# PIO-Dev-3.net
KiCad netlist of a schematic drawn in EAGLE
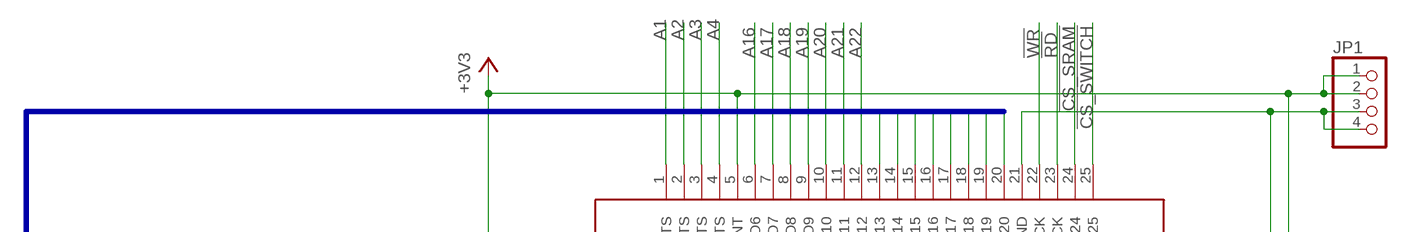
[diagram p0: schematic, sheet 1, part 1 of 3]
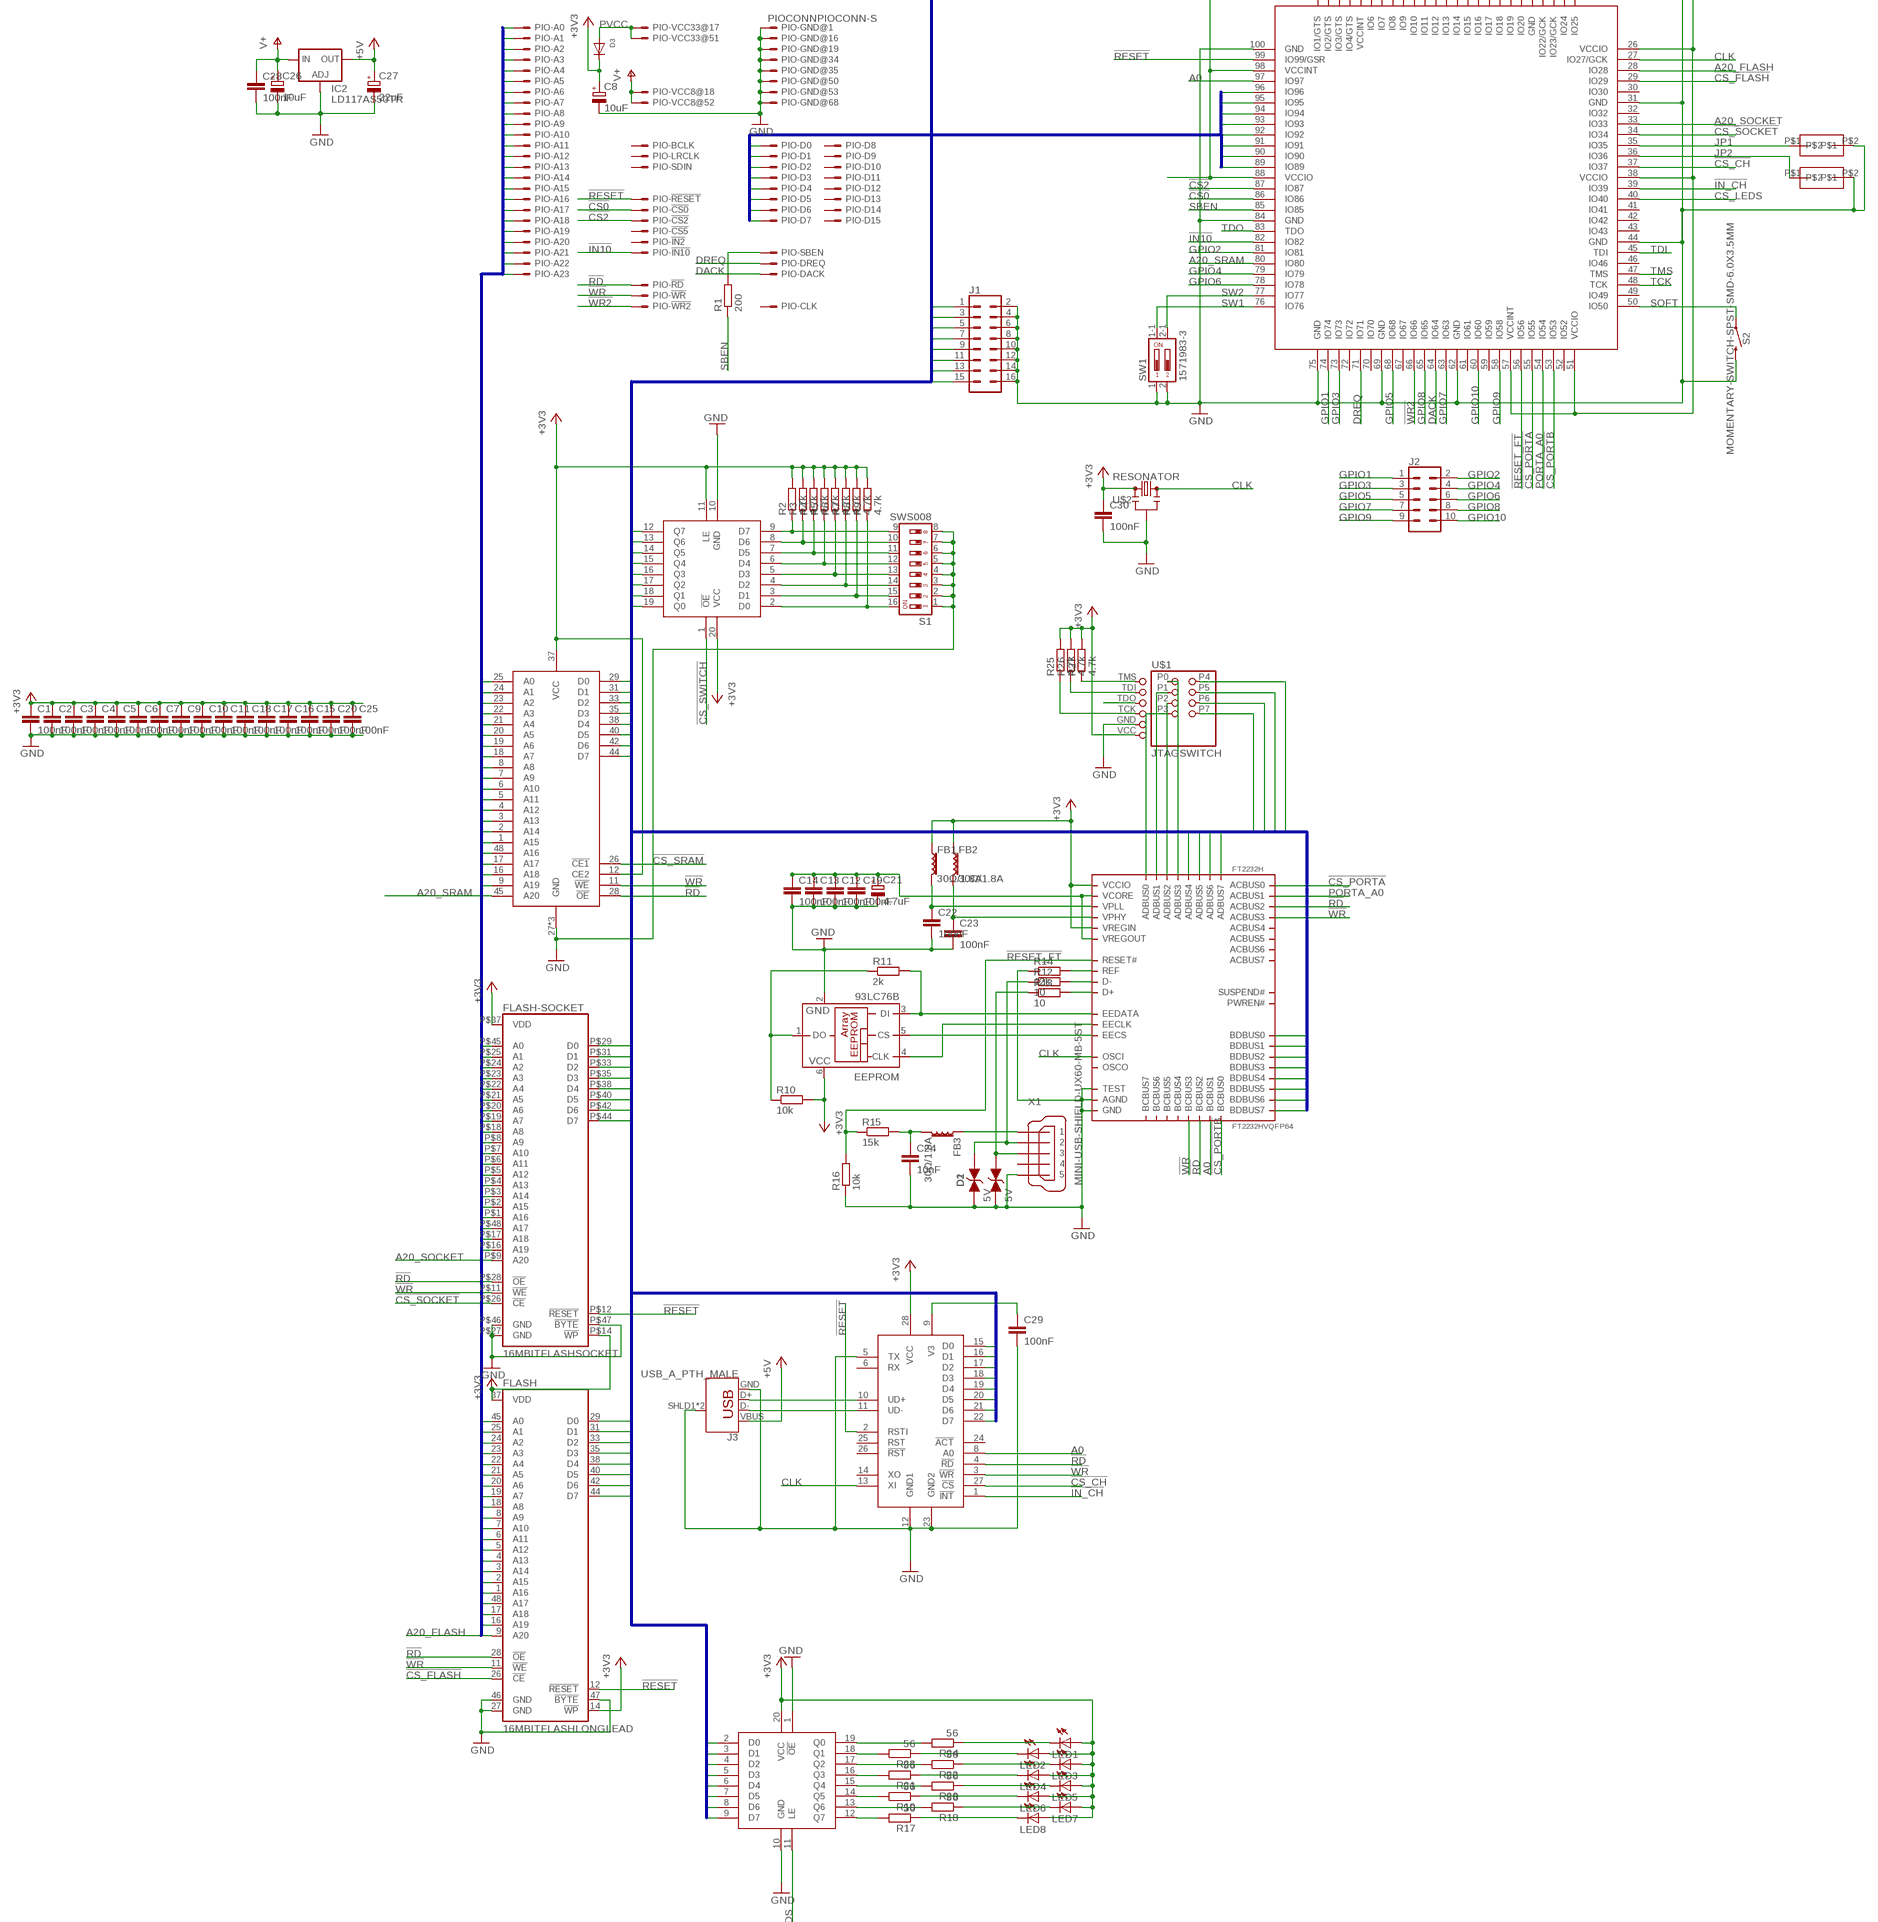
[diagram p1: schematic, sheet 1, part 2 of 3]
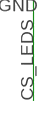
[diagram p2: schematic, sheet 1, part 3 of 3]

(export (version "E")
  (design (tool "Eeschema 10.0.6"))
  (components
    (comp (ref "C1")
      (value "100nF")
      (footprint "eagle-import:C0402K")
      (libsource (lib "eagle-import") (part "C-EUC0402K"))
    )
    (comp (ref "C2")
      (value "100nF")
      (footprint "eagle-import:C0402K")
      (libsource (lib "eagle-import") (part "C-EUC0402K"))
    )
    (comp (ref "C3")
      (value "100nF")
      (footprint "eagle-import:C0402K")
      (libsource (lib "eagle-import") (part "C-EUC0402K"))
    )
    (comp (ref "C4")
      (value "100nF")
      (footprint "eagle-import:C0402K")
      (libsource (lib "eagle-import") (part "C-EUC0402K"))
    )
    (comp (ref "C5")
      (value "100nF")
      (footprint "eagle-import:C0402K")
      (libsource (lib "eagle-import") (part "C-EUC0402K"))
    )
    (comp (ref "C6")
      (value "100nF")
      (footprint "eagle-import:C0402K")
      (libsource (lib "eagle-import") (part "C-EUC0402K"))
    )
    (comp (ref "C7")
      (value "100nF")
      (footprint "eagle-import:C0402K")
      (libsource (lib "eagle-import") (part "C-EUC0402K"))
    )
    (comp (ref "C8")
      (value "10uF")
      (footprint "eagle-import:A_3216-18W")
      (libsource (lib "eagle-import") (part "CPOL-EUA/3216-18W"))
    )
    (comp (ref "C9")
      (value "100nF")
      (footprint "eagle-import:C0402K")
      (libsource (lib "eagle-import") (part "C-EUC0402K"))
    )
    (comp (ref "C10")
      (value "100nF")
      (footprint "eagle-import:C0402K")
      (libsource (lib "eagle-import") (part "C-EUC0402K"))
    )
    (comp (ref "C11")
      (value "100nF")
      (footprint "eagle-import:C0402K")
      (libsource (lib "eagle-import") (part "C-EUC0402K"))
    )
    (comp (ref "C12")
      (value "100nF")
      (footprint "eagle-import:C0603K")
      (libsource (lib "eagle-import") (part "C-EUC0603K"))
    )
    (comp (ref "C13")
      (value "100nF")
      (footprint "eagle-import:C0603K")
      (libsource (lib "eagle-import") (part "C-EUC0603K"))
    )
    (comp (ref "C14")
      (value "100nF")
      (footprint "eagle-import:C0603K")
      (libsource (lib "eagle-import") (part "C-EUC0603K"))
    )
    (comp (ref "C15")
      (value "100nF")
      (footprint "eagle-import:C0603K")
      (libsource (lib "eagle-import") (part "C-EUC0603K"))
    )
    (comp (ref "C16")
      (value "100nF")
      (footprint "eagle-import:C0603K")
      (libsource (lib "eagle-import") (part "C-EUC0603K"))
    )
    (comp (ref "C17")
      (value "100nF")
      (footprint "eagle-import:C0603K")
      (libsource (lib "eagle-import") (part "C-EUC0603K"))
    )
    (comp (ref "C18")
      (value "100nF")
      (footprint "eagle-import:C0603K")
      (libsource (lib "eagle-import") (part "C-EUC0603K"))
    )
    (comp (ref "C19")
      (value "100nF")
      (footprint "eagle-import:C0603K")
      (libsource (lib "eagle-import") (part "C-EUC0603K"))
    )
    (comp (ref "C20")
      (value "100nF")
      (footprint "eagle-import:C0603K")
      (libsource (lib "eagle-import") (part "C-EUC0603K"))
    )
    (comp (ref "C21")
      (value "4.7uF")
      (footprint "eagle-import:A_3216-18W")
      (libsource (lib "eagle-import") (part "CPOL-EUA/3216-18W"))
    )
    (comp (ref "C22")
      (value "100nF")
      (footprint "eagle-import:C0603K")
      (libsource (lib "eagle-import") (part "C-EUC0603K"))
    )
    (comp (ref "C23")
      (value "100nF")
      (footprint "eagle-import:C0603K")
      (libsource (lib "eagle-import") (part "C-EUC0603K"))
    )
    (comp (ref "C24")
      (value "10nF")
      (footprint "eagle-import:C0402K")
      (libsource (lib "eagle-import") (part "C-EUC0402K"))
    )
    (comp (ref "C25")
      (value "100nF")
      (footprint "eagle-import:C0402K")
      (libsource (lib "eagle-import") (part "C-EUC0402K"))
    )
    (comp (ref "C26")
      (value "10uF")
      (footprint "eagle-import:A_3216-18W")
      (libsource (lib "eagle-import") (part "CPOL-EUA/3216-18W"))
    )
    (comp (ref "C27")
      (value "22uF")
      (footprint "eagle-import:A_3216-18W")
      (libsource (lib "eagle-import") (part "CPOL-EUA/3216-18W"))
    )
    (comp (ref "C28")
      (value "100nF")
      (footprint "eagle-import:C0603K")
      (libsource (lib "eagle-import") (part "C-EUC0603K"))
    )
    (comp (ref "C29")
      (value "100nF")
      (footprint "eagle-import:C0402K")
      (libsource (lib "eagle-import") (part "C-EUC0402K"))
    )
    (comp (ref "C30")
      (value "100nF")
      (footprint "eagle-import:C0603K")
      (libsource (lib "eagle-import") (part "C-EUC0603K"))
    )
    (comp (ref "CH")
      (value "CH375B")
      (footprint "eagle-import:SOP28-LL")
      (libsource (lib "eagle-import") (part "CH375B"))
    )
    (comp (ref "CPLD")
      (value "XC95144XL-100")
      (footprint "eagle-import:TQFP100")
      (libsource (lib "eagle-import") (part "XC95144XL-100"))
    )
    (comp (ref "D1")
      (value "5V")
      (footprint "eagle-import:WE-VE_0603")
      (libsource (lib "eagle-import") (part "WE-VE_0603_82356050050"))
    )
    (comp (ref "D2")
      (value "5V")
      (footprint "eagle-import:WE-VE_0603")
      (libsource (lib "eagle-import") (part "WE-VE_0603_82356050050"))
    )
    (comp (ref "D3")
      (value "DIODESOD-123")
      (footprint "eagle-import:SOD-123")
      (libsource (lib "eagle-import") (part "DIODESOD-123"))
    )
    (comp (ref "EEPROM")
      (value "93LC76B")
      (footprint "eagle-import:SOT23-6")
      (fields (field (name "MF") "MICROCHIP") (field (name "MPN") "93LC76BT-I/OT"))
      (libsource (lib "eagle-import") (part "9376?BLC"))
    )
    (comp (ref "FB1")
      (value "30Ω/1.8A")
      (footprint "eagle-import:0603")
      (libsource (lib "eagle-import") (part "FERRITE_BEAD-0603"))
    )
    (comp (ref "FB2")
      (value "30Ω/1.8A")
      (footprint "eagle-import:0603")
      (libsource (lib "eagle-import") (part "FERRITE_BEAD-0603"))
    )
    (comp (ref "FB3")
      (value "30Ω/1.8A")
      (footprint "eagle-import:0603")
      (libsource (lib "eagle-import") (part "FERRITE_BEAD-0603"))
    )
    (comp (ref "FLASH")
      (value "16MBITFLASHLONGLEAD")
      (footprint "eagle-import:TSOP48-LL")
      (libsource (lib "eagle-import") (part "16MBITFLASHLONGLEAD"))
    )
    (comp (ref "FLASH-SOCKET")
      (value "16MBITFLASHSOCKET")
      (footprint "eagle-import:TSOP48-ADAPTER")
      (libsource (lib "eagle-import") (part "16MBITFLASHSOCKET"))
    )
    (comp (ref "FT2232H")
      (value "FT2232HVQFP64")
      (footprint "eagle-import:VQFP64")
      (libsource (lib "eagle-import") (part "FT2232HVQFP64"))
    )
    (comp (ref "IC2")
      (value "LD117AS50TR")
      (footprint "eagle-import:SOT223")
      (libsource (lib "eagle-import") (part "LD117A?S50TR"))
    )
    (comp (ref "J1")
      (value "CONN_08X2SHD_SMD")
      (footprint "eagle-import:2X8-SHROUDED_SMD")
      (libsource (lib "eagle-import") (part "CONN_08X2SHD_SMD"))
    )
    (comp (ref "J2")
      (value "CONN_05X2SHD_SMD")
      (footprint "eagle-import:2X5-SHROUDED_SMD")
      (libsource (lib "eagle-import") (part "CONN_05X2SHD_SMD"))
    )
    (comp (ref "J3")
      (value "USB_A_PTH_MALE")
      (footprint "eagle-import:USB-A-H")
      (libsource (lib "eagle-import") (part "USB_A_PTH_MALE"))
    )
    (comp (ref "JP1")
      (value "PINHD-1X4")
      (footprint "eagle-import:1X04")
      (libsource (lib "eagle-import") (part "PINHD-1X4"))
    )
    (comp (ref "LED1")
      (value "LEDCHIPLED_1206")
      (footprint "eagle-import:CHIPLED_1206")
      (libsource (lib "eagle-import") (part "LEDCHIPLED_1206"))
    )
    (comp (ref "LED2")
      (value "LEDCHIPLED_1206")
      (footprint "eagle-import:CHIPLED_1206")
      (libsource (lib "eagle-import") (part "LEDCHIPLED_1206"))
    )
    (comp (ref "LED3")
      (value "LEDCHIPLED_1206")
      (footprint "eagle-import:CHIPLED_1206")
      (libsource (lib "eagle-import") (part "LEDCHIPLED_1206"))
    )
    (comp (ref "LED4")
      (value "LEDCHIPLED_1206")
      (footprint "eagle-import:CHIPLED_1206")
      (libsource (lib "eagle-import") (part "LEDCHIPLED_1206"))
    )
    (comp (ref "LED5")
      (value "LEDCHIPLED_1206")
      (footprint "eagle-import:CHIPLED_1206")
      (libsource (lib "eagle-import") (part "LEDCHIPLED_1206"))
    )
    (comp (ref "LED6")
      (value "LEDCHIPLED_1206")
      (footprint "eagle-import:CHIPLED_1206")
      (libsource (lib "eagle-import") (part "LEDCHIPLED_1206"))
    )
    (comp (ref "LED7")
      (value "LEDCHIPLED_1206")
      (footprint "eagle-import:CHIPLED_1206")
      (libsource (lib "eagle-import") (part "LEDCHIPLED_1206"))
    )
    (comp (ref "LED8")
      (value "LEDCHIPLED_1206")
      (footprint "eagle-import:CHIPLED_1206")
      (libsource (lib "eagle-import") (part "LEDCHIPLED_1206"))
    )
    (comp (ref "LEDS")
      (value "74LVC573APW")
      (footprint "eagle-import:TSSOP20-LL")
      (libsource (lib "eagle-import") (part "74LVC573APW"))
    )
    (comp (ref "PIO")
      (value "PIOCONNPIOCONN-S")
      (footprint "eagle-import:PIOCONN")
      (libsource (lib "eagle-import") (part "PIOCONNPIOCONN-S"))
    )
    (comp (ref "R1")
      (value "200")
      (footprint "eagle-import:R0402")
      (libsource (lib "eagle-import") (part "R-EU_R0402"))
    )
    (comp (ref "R2")
      (value "4.7k")
      (footprint "eagle-import:R0402")
      (libsource (lib "eagle-import") (part "R-EU_R0402"))
    )
    (comp (ref "R3")
      (value "4.7k")
      (footprint "eagle-import:R0402")
      (libsource (lib "eagle-import") (part "R-EU_R0402"))
    )
    (comp (ref "R4")
      (value "4.7k")
      (footprint "eagle-import:R0402")
      (libsource (lib "eagle-import") (part "R-EU_R0402"))
    )
    (comp (ref "R5")
      (value "4.7k")
      (footprint "eagle-import:R0402")
      (libsource (lib "eagle-import") (part "R-EU_R0402"))
    )
    (comp (ref "R6")
      (value "4.7k")
      (footprint "eagle-import:R0402")
      (libsource (lib "eagle-import") (part "R-EU_R0402"))
    )
    (comp (ref "R7")
      (value "4.7k")
      (footprint "eagle-import:R0402")
      (libsource (lib "eagle-import") (part "R-EU_R0402"))
    )
    (comp (ref "R8")
      (value "4.7k")
      (footprint "eagle-import:R0402")
      (libsource (lib "eagle-import") (part "R-EU_R0402"))
    )
    (comp (ref "R9")
      (value "4.7k")
      (footprint "eagle-import:R0402")
      (libsource (lib "eagle-import") (part "R-EU_R0402"))
    )
    (comp (ref "R10")
      (value "10k")
      (footprint "eagle-import:R0402")
      (libsource (lib "eagle-import") (part "R-EU_R0402"))
    )
    (comp (ref "R11")
      (value "2k")
      (footprint "eagle-import:R0402")
      (libsource (lib "eagle-import") (part "R-EU_R0402"))
    )
    (comp (ref "R12")
      (value "10")
      (footprint "eagle-import:R0402")
      (libsource (lib "eagle-import") (part "R-EU_R0402"))
    )
    (comp (ref "R13")
      (value "10")
      (footprint "eagle-import:R0402")
      (libsource (lib "eagle-import") (part "R-EU_R0402"))
    )
    (comp (ref "R14")
      (value "12k")
      (footprint "eagle-import:R0402")
      (libsource (lib "eagle-import") (part "R-EU_R0402"))
    )
    (comp (ref "R15")
      (value "15k")
      (footprint "eagle-import:R0402")
      (libsource (lib "eagle-import") (part "R-EU_R0402"))
    )
    (comp (ref "R16")
      (value "10k")
      (footprint "eagle-import:R0402")
      (libsource (lib "eagle-import") (part "R-EU_R0402"))
    )
    (comp (ref "R17")
      (value "56")
      (footprint "eagle-import:R0603")
      (libsource (lib "eagle-import") (part "R-EU_R0603"))
    )
    (comp (ref "R18")
      (value "56")
      (footprint "eagle-import:R0603")
      (libsource (lib "eagle-import") (part "R-EU_R0603"))
    )
    (comp (ref "R19")
      (value "56")
      (footprint "eagle-import:R0603")
      (libsource (lib "eagle-import") (part "R-EU_R0603"))
    )
    (comp (ref "R20")
      (value "56")
      (footprint "eagle-import:R0603")
      (libsource (lib "eagle-import") (part "R-EU_R0603"))
    )
    (comp (ref "R21")
      (value "56")
      (footprint "eagle-import:R0603")
      (libsource (lib "eagle-import") (part "R-EU_R0603"))
    )
    (comp (ref "R22")
      (value "56")
      (footprint "eagle-import:R0603")
      (libsource (lib "eagle-import") (part "R-EU_R0603"))
    )
    (comp (ref "R23")
      (value "56")
      (footprint "eagle-import:R0603")
      (libsource (lib "eagle-import") (part "R-EU_R0603"))
    )
    (comp (ref "R24")
      (value "56")
      (footprint "eagle-import:R0603")
      (libsource (lib "eagle-import") (part "R-EU_R0603"))
    )
    (comp (ref "R25")
      (value "4.7k")
      (footprint "eagle-import:R0402")
      (libsource (lib "eagle-import") (part "R-EU_R0402"))
    )
    (comp (ref "R26")
      (value "4.7k")
      (footprint "eagle-import:R0402")
      (libsource (lib "eagle-import") (part "R-EU_R0402"))
    )
    (comp (ref "R27")
      (value "4.7k")
      (footprint "eagle-import:R0402")
      (libsource (lib "eagle-import") (part "R-EU_R0402"))
    )
    (comp (ref "S1")
      (value "SWS008")
      (footprint "eagle-import:SMS-008")
      (libsource (lib "eagle-import") (part "SWS008"))
    )
    (comp (ref "S2")
      (value "MOMENTARY-SWITCH-SPST-SMD-6.0X3.5MM")
      (footprint "eagle-import:TACTILE_SWITCH_SMD_6.0X3.5MM")
      (libsource (lib "eagle-import") (part "MOMENTARY-SWITCH-SPST-SMD-6.0X3.5MM"))
    )
    (comp (ref "SRAM")
      (value "CY62167EV30LL")
      (footprint "eagle-import:TSOP48-LL")
      (libsource (lib "eagle-import") (part "CY62167EV30LL"))
    )
    (comp (ref "SW1")
      (value "1571983-3")
      (footprint "eagle-import:1571983-3")
      (fields
        (field (name "DIGIKEY_PARTNO") "450-2128-2-ND")
        (field (name "MANUFACTURER") "TE Connectivity ALCOSWITCH Switches")
        (field (name "CREATED_BY") "PCBLayout.com")
      )
      (libsource (lib "eagle-import") (part "1571983-3"))
    )
    (comp (ref "SWITCH")
      (value "74LVC573APW")
      (footprint "eagle-import:TSSOP20-LL")
      (libsource (lib "eagle-import") (part "74LVC573APW"))
    )
    (comp (ref "U$1")
      (value "JTAGSWITCH")
      (footprint "eagle-import:JTAGSWITCH")
      (libsource (lib "eagle-import") (part "JTAGSWITCH"))
    )
    (comp (ref "U$2")
      (value "RESONATOR")
      (footprint "eagle-import:RESONATOR")
      (libsource (lib "eagle-import") (part "RESONATOR"))
    )
    (comp (ref "U$3")
      (value "SMD-JUMPER")
      (footprint "eagle-import:SMD-JUMPER")
      (libsource (lib "eagle-import") (part "SMD-JUMPER"))
    )
    (comp (ref "U$4")
      (value "SMD-JUMPER")
      (footprint "eagle-import:SMD-JUMPER")
      (libsource (lib "eagle-import") (part "SMD-JUMPER"))
    )
    (comp (ref "X1")
      (value "MINI-USB-SHIELD-UX60-MB-5ST")
      (footprint "eagle-import:UX60-MB-5ST")
      (libsource (lib "eagle-import") (part "MINI-USB-SHIELD-UX60-MB-5ST"))
    )
  )
  (nets
    (net (code "1") (name "+3V3") (class "Default")
      (node (ref "C1") (pin "1") (pinfunction "1_1") (pintype "passive"))
      (node (ref "C10") (pin "1") (pinfunction "1_1") (pintype "passive"))
      (node (ref "C11") (pin "1") (pinfunction "1_1") (pintype "passive"))
      (node (ref "C15") (pin "1") (pinfunction "1_1") (pintype "passive"))
      (node (ref "C16") (pin "1") (pinfunction "1_1") (pintype "passive"))
      (node (ref "C17") (pin "1") (pinfunction "1_1") (pintype "passive"))
      (node (ref "C18") (pin "1") (pinfunction "1_1") (pintype "passive"))
      (node (ref "C2") (pin "1") (pinfunction "1_1") (pintype "passive"))
      (node (ref "C20") (pin "1") (pinfunction "1_1") (pintype "passive"))
      (node (ref "C25") (pin "1") (pinfunction "1_1") (pintype "passive"))
      (node (ref "C3") (pin "1") (pinfunction "1_1") (pintype "passive"))
      (node (ref "C30") (pin "1") (pinfunction "1_1") (pintype "passive"))
      (node (ref "C4") (pin "1") (pinfunction "1_1") (pintype "passive"))
      (node (ref "C5") (pin "1") (pinfunction "1_1") (pintype "passive"))
      (node (ref "C6") (pin "1") (pinfunction "1_1") (pintype "passive"))
      (node (ref "C7") (pin "1") (pinfunction "1_1") (pintype "passive"))
      (node (ref "C8") (pin "+") (pinfunction "+_+") (pintype "passive"))
      (node (ref "C9") (pin "1") (pinfunction "1_1") (pintype "passive"))
      (node (ref "CH") (pin "28") (pinfunction "VCC_28") (pintype "bidirectional"))
      (node (ref "CPLD") (pin "26") (pinfunction "VCCIO_26") (pintype "bidirectional"))
      (node (ref "CPLD") (pin "38") (pinfunction "VCCIO_38") (pintype "bidirectional"))
      (node (ref "CPLD") (pin "5") (pinfunction "VCCINT_5") (pintype "bidirectional"))
      (node (ref "CPLD") (pin "51") (pinfunction "VCCIO_51") (pintype "bidirectional"))
      (node (ref "CPLD") (pin "57") (pinfunction "VCCINT_57") (pintype "bidirectional"))
      (node (ref "CPLD") (pin "88") (pinfunction "VCCIO_88") (pintype "bidirectional"))
      (node (ref "CPLD") (pin "98") (pinfunction "VCCINT_98") (pintype "bidirectional"))
      (node (ref "D3") (pin "C") (pinfunction "C_C") (pintype "passive"))
      (node (ref "EEPROM") (pin "6") (pinfunction "VCC_6") (pintype "power_in"))
      (node (ref "FB1") (pin "1") (pinfunction "1_1") (pintype "passive"))
      (node (ref "FB2") (pin "1") (pinfunction "1_1") (pintype "passive"))
      (node (ref "FLASH") (pin "14") (pinfunction "~{WP}_14") (pintype "bidirectional"))
      (node (ref "FLASH") (pin "37") (pinfunction "VDD_37") (pintype "power_in"))
      (node (ref "FLASH-SOCKET") (pin "P$14") (pinfunction "~{WP}_P$14") (pintype "bidirectional"))
      (node (ref "FLASH-SOCKET") (pin "P$37") (pinfunction "VDD_P$37") (pintype "power_in"))
      (node (ref "FT2232H") (pin "20") (pinfunction "VCCIO_20") (pintype "bidirectional"))
      (node (ref "FT2232H") (pin "31") (pinfunction "VCCIO_31") (pintype "bidirectional"))
      (node (ref "FT2232H") (pin "42") (pinfunction "VCCIO_42") (pintype "bidirectional"))
      (node (ref "FT2232H") (pin "50") (pinfunction "VREGIN_50") (pintype "bidirectional"))
      (node (ref "FT2232H") (pin "56") (pinfunction "VCCIO_56") (pintype "bidirectional"))
      (node (ref "JP1") (pin "1") (pinfunction "1_1") (pintype "passive"))
      (node (ref "JP1") (pin "2") (pinfunction "2_2") (pintype "passive"))
      (node (ref "LED1") (pin "A") (pinfunction "A_A") (pintype "passive"))
      (node (ref "LED2") (pin "A") (pinfunction "A_A") (pintype "passive"))
      (node (ref "LED3") (pin "A") (pinfunction "A_A") (pintype "passive"))
      (node (ref "LED4") (pin "A") (pinfunction "A_A") (pintype "passive"))
      (node (ref "LED5") (pin "A") (pinfunction "A_A") (pintype "passive"))
      (node (ref "LED6") (pin "A") (pinfunction "A_A") (pintype "passive"))
      (node (ref "LED7") (pin "A") (pinfunction "A_A") (pintype "passive"))
      (node (ref "LED8") (pin "A") (pinfunction "A_A") (pintype "passive"))
      (node (ref "LEDS") (pin "20") (pinfunction "VCC_20") (pintype "bidirectional"))
      (node (ref "R10") (pin "2") (pinfunction "2_2") (pintype "passive"))
      (node (ref "R2") (pin "2") (pinfunction "2_2") (pintype "passive"))
      (node (ref "R25") (pin "2") (pinfunction "2_2") (pintype "passive"))
      (node (ref "R26") (pin "2") (pinfunction "2_2") (pintype "passive"))
      (node (ref "R27") (pin "2") (pinfunction "2_2") (pintype "passive"))
      (node (ref "R3") (pin "2") (pinfunction "2_2") (pintype "passive"))
      (node (ref "R4") (pin "2") (pinfunction "2_2") (pintype "passive"))
      (node (ref "R5") (pin "2") (pinfunction "2_2") (pintype "passive"))
      (node (ref "R6") (pin "2") (pinfunction "2_2") (pintype "passive"))
      (node (ref "R7") (pin "2") (pinfunction "2_2") (pintype "passive"))
      (node (ref "R8") (pin "2") (pinfunction "2_2") (pintype "passive"))
      (node (ref "R9") (pin "2") (pinfunction "2_2") (pintype "passive"))
      (node (ref "SRAM") (pin "12") (pinfunction "CE2_12") (pintype "bidirectional"))
      (node (ref "SRAM") (pin "37") (pinfunction "VCC_37") (pintype "bidirectional"))
      (node (ref "SWITCH") (pin "11") (pinfunction "LE_11") (pintype "bidirectional"))
      (node (ref "SWITCH") (pin "20") (pinfunction "VCC_20") (pintype "bidirectional"))
      (node (ref "U$1") (pin "VCC") (pinfunction "VCC_VCC") (pintype "passive"))
      (node (ref "U$2") (pin "P4") (pinfunction "VDD_P4") (pintype "passive"))
    )
    (net (code "2") (name "+5V") (class "Default")
      (node (ref "C27") (pin "+") (pinfunction "+_+") (pintype "passive"))
      (node (ref "IC2") (pin "4") (pinfunction "OUT_4") (pintype "passive"))
      (node (ref "J3") (pin "VBUS") (pinfunction "VBUS_VBUS") (pintype "power_in"))
    )
    (net (code "3") (name "/A0") (class "Default")
      (node (ref "CH") (pin "8") (pinfunction "A0_8") (pintype "bidirectional"))
      (node (ref "CPLD") (pin "97") (pinfunction "IO97_97") (pintype "bidirectional"))
      (node (ref "FLASH") (pin "45") (pinfunction "A0_45") (pintype "input"))
      (node (ref "FLASH-SOCKET") (pin "P$45") (pinfunction "A0_P$45") (pintype "input"))
      (node (ref "FT2232H") (pin "52") (pinfunction "BCBUS1_52") (pintype "bidirectional"))
      (node (ref "PIO") (pin "14") (pinfunction "S_14") (pintype "passive"))
      (node (ref "SRAM") (pin "25") (pinfunction "A0_25") (pintype "bidirectional"))
    )
    (net (code "4") (name "/A1") (class "Default")
      (node (ref "CPLD") (pin "1") (pinfunction "IO1/GTS_1") (pintype "bidirectional"))
      (node (ref "FLASH") (pin "25") (pinfunction "A1_25") (pintype "input"))
      (node (ref "FLASH-SOCKET") (pin "P$25") (pinfunction "A1_P$25") (pintype "input"))
      (node (ref "PIO") (pin "48") (pinfunction "S_48") (pintype "passive"))
      (node (ref "SRAM") (pin "24") (pinfunction "A1_24") (pintype "bidirectional"))
    )
    (net (code "5") (name "/A2") (class "Default")
      (node (ref "CPLD") (pin "2") (pinfunction "IO2/GTS_2") (pintype "bidirectional"))
      (node (ref "FLASH") (pin "24") (pinfunction "A2_24") (pintype "input"))
      (node (ref "FLASH-SOCKET") (pin "P$24") (pinfunction "A2_P$24") (pintype "input"))
      (node (ref "PIO") (pin "15") (pinfunction "S_15") (pintype "passive"))
      (node (ref "SRAM") (pin "23") (pinfunction "A2_23") (pintype "bidirectional"))
    )
    (net (code "6") (name "/A3") (class "Default")
      (node (ref "CPLD") (pin "3") (pinfunction "IO3/GTS_3") (pintype "bidirectional"))
      (node (ref "FLASH") (pin "23") (pinfunction "A3_23") (pintype "input"))
      (node (ref "FLASH-SOCKET") (pin "P$23") (pinfunction "A3_P$23") (pintype "input"))
      (node (ref "PIO") (pin "49") (pinfunction "S_49") (pintype "passive"))
      (node (ref "SRAM") (pin "22") (pinfunction "A3_22") (pintype "bidirectional"))
    )
    (net (code "7") (name "/A4") (class "Default")
      (node (ref "CPLD") (pin "4") (pinfunction "IO4/GTS_4") (pintype "bidirectional"))
      (node (ref "FLASH") (pin "22") (pinfunction "A4_22") (pintype "input"))
      (node (ref "FLASH-SOCKET") (pin "P$22") (pinfunction "A4_P$22") (pintype "input"))
      (node (ref "PIO") (pin "20") (pinfunction "S_20") (pintype "passive"))
      (node (ref "SRAM") (pin "21") (pinfunction "A4_21") (pintype "bidirectional"))
    )
    (net (code "8") (name "/A5") (class "Default")
      (node (ref "FLASH") (pin "21") (pinfunction "A5_21") (pintype "input"))
      (node (ref "FLASH-SOCKET") (pin "P$21") (pinfunction "A5_P$21") (pintype "input"))
      (node (ref "PIO") (pin "54") (pinfunction "S_54") (pintype "passive"))
      (node (ref "SRAM") (pin "20") (pinfunction "A5_20") (pintype "bidirectional"))
    )
    (net (code "9") (name "/A6") (class "Default")
      (node (ref "FLASH") (pin "20") (pinfunction "A6_20") (pintype "input"))
      (node (ref "FLASH-SOCKET") (pin "P$20") (pinfunction "A6_P$20") (pintype "input"))
      (node (ref "PIO") (pin "21") (pinfunction "S_21") (pintype "passive"))
      (node (ref "SRAM") (pin "19") (pinfunction "A6_19") (pintype "bidirectional"))
    )
    (net (code "10") (name "/A7") (class "Default")
      (node (ref "FLASH") (pin "19") (pinfunction "A7_19") (pintype "input"))
      (node (ref "FLASH-SOCKET") (pin "P$19") (pinfunction "A7_P$19") (pintype "input"))
      (node (ref "PIO") (pin "55") (pinfunction "S_55") (pintype "passive"))
      (node (ref "SRAM") (pin "18") (pinfunction "A7_18") (pintype "bidirectional"))
    )
    (net (code "11") (name "/A8") (class "Default")
      (node (ref "FLASH") (pin "18") (pinfunction "A8_18") (pintype "input"))
      (node (ref "FLASH-SOCKET") (pin "P$18") (pinfunction "A8_P$18") (pintype "input"))
      (node (ref "PIO") (pin "22") (pinfunction "S_22") (pintype "passive"))
      (node (ref "SRAM") (pin "8") (pinfunction "A8_8") (pintype "bidirectional"))
    )
    (net (code "12") (name "/A9") (class "Default")
      (node (ref "FLASH") (pin "8") (pinfunction "A9_8") (pintype "input"))
      (node (ref "FLASH-SOCKET") (pin "P$8") (pinfunction "A9_P$8") (pintype "input"))
      (node (ref "PIO") (pin "56") (pinfunction "S_56") (pintype "passive"))
      (node (ref "SRAM") (pin "7") (pinfunction "A9_7") (pintype "bidirectional"))
    )
    (net (code "13") (name "/A10") (class "Default")
      (node (ref "FLASH") (pin "7") (pinfunction "A10_7") (pintype "input"))
      (node (ref "FLASH-SOCKET") (pin "P$7") (pinfunction "A10_P$7") (pintype "input"))
      (node (ref "PIO") (pin "23") (pinfunction "S_23") (pintype "passive"))
      (node (ref "SRAM") (pin "6") (pinfunction "A10_6") (pintype "bidirectional"))
    )
    (net (code "14") (name "/A11") (class "Default")
      (node (ref "FLASH") (pin "6") (pinfunction "A11_6") (pintype "input"))
      (node (ref "FLASH-SOCKET") (pin "P$6") (pinfunction "A11_P$6") (pintype "input"))
      (node (ref "PIO") (pin "57") (pinfunction "S_57") (pintype "passive"))
      (node (ref "SRAM") (pin "5") (pinfunction "A11_5") (pintype "bidirectional"))
    )
    (net (code "15") (name "/A12") (class "Default")
      (node (ref "FLASH") (pin "5") (pinfunction "A12_5") (pintype "input"))
      (node (ref "FLASH-SOCKET") (pin "P$5") (pinfunction "A12_P$5") (pintype "input"))
      (node (ref "PIO") (pin "24") (pinfunction "S_24") (pintype "passive"))
      (node (ref "SRAM") (pin "4") (pinfunction "A12_4") (pintype "bidirectional"))
    )
    (net (code "16") (name "/A13") (class "Default")
      (node (ref "FLASH") (pin "4") (pinfunction "A13_4") (pintype "input"))
      (node (ref "FLASH-SOCKET") (pin "P$4") (pinfunction "A13_P$4") (pintype "input"))
      (node (ref "PIO") (pin "58") (pinfunction "S_58") (pintype "passive"))
      (node (ref "SRAM") (pin "3") (pinfunction "A13_3") (pintype "bidirectional"))
    )
    (net (code "17") (name "/A14") (class "Default")
      (node (ref "FLASH") (pin "3") (pinfunction "A14_3") (pintype "input"))
      (node (ref "FLASH-SOCKET") (pin "P$3") (pinfunction "A14_P$3") (pintype "input"))
      (node (ref "PIO") (pin "25") (pinfunction "S_25") (pintype "passive"))
      (node (ref "SRAM") (pin "2") (pinfunction "A14_2") (pintype "bidirectional"))
    )
    (net (code "18") (name "/A15") (class "Default")
      (node (ref "FLASH") (pin "2") (pinfunction "A15_2") (pintype "input"))
      (node (ref "FLASH-SOCKET") (pin "P$2") (pinfunction "A15_P$2") (pintype "input"))
      (node (ref "PIO") (pin "59") (pinfunction "S_59") (pintype "passive"))
      (node (ref "SRAM") (pin "1") (pinfunction "A15_1") (pintype "bidirectional"))
    )
    (net (code "19") (name "/A16") (class "Default")
      (node (ref "CPLD") (pin "6") (pinfunction "IO6_6") (pintype "bidirectional"))
      (node (ref "FLASH") (pin "1") (pinfunction "A16_1") (pintype "input"))
      (node (ref "FLASH-SOCKET") (pin "P$1") (pinfunction "A16_P$1") (pintype "input"))
      (node (ref "PIO") (pin "26") (pinfunction "S_26") (pintype "passive"))
      (node (ref "SRAM") (pin "48") (pinfunction "A16_48") (pintype "bidirectional"))
    )
    (net (code "20") (name "/A17") (class "Default")
      (node (ref "CPLD") (pin "7") (pinfunction "IO7_7") (pintype "bidirectional"))
      (node (ref "FLASH") (pin "48") (pinfunction "A17_48") (pintype "input"))
      (node (ref "FLASH-SOCKET") (pin "P$48") (pinfunction "A17_P$48") (pintype "input"))
      (node (ref "PIO") (pin "60") (pinfunction "S_60") (pintype "passive"))
      (node (ref "SRAM") (pin "17") (pinfunction "A17_17") (pintype "bidirectional"))
    )
    (net (code "21") (name "/A18") (class "Default")
      (node (ref "CPLD") (pin "8") (pinfunction "IO8_8") (pintype "bidirectional"))
      (node (ref "FLASH") (pin "17") (pinfunction "A18_17") (pintype "input"))
      (node (ref "FLASH-SOCKET") (pin "P$17") (pinfunction "A18_P$17") (pintype "input"))
      (node (ref "PIO") (pin "27") (pinfunction "S_27") (pintype "passive"))
      (node (ref "SRAM") (pin "16") (pinfunction "A18_16") (pintype "bidirectional"))
    )
    (net (code "22") (name "/A19") (class "Default")
      (node (ref "CPLD") (pin "9") (pinfunction "IO9_9") (pintype "bidirectional"))
      (node (ref "FLASH") (pin "16") (pinfunction "A19_16") (pintype "bidirectional"))
      (node (ref "FLASH-SOCKET") (pin "P$16") (pinfunction "A19_P$16") (pintype "bidirectional"))
      (node (ref "PIO") (pin "61") (pinfunction "S_61") (pintype "passive"))
      (node (ref "SRAM") (pin "9") (pinfunction "A19_9") (pintype "bidirectional"))
    )
    (net (code "23") (name "/A20") (class "Default")
      (node (ref "CPLD") (pin "10") (pinfunction "IO10_10") (pintype "bidirectional"))
      (node (ref "PIO") (pin "28") (pinfunction "S_28") (pintype "passive"))
    )
    (net (code "24") (name "/A20_FLASH") (class "Default")
      (node (ref "CPLD") (pin "28") (pinfunction "IO28_28") (pintype "bidirectional"))
      (node (ref "FLASH") (pin "9") (pinfunction "A20_9") (pintype "bidirectional"))
    )
    (net (code "25") (name "/A20_SOCKET") (class "Default")
      (node (ref "CPLD") (pin "33") (pinfunction "IO33_33") (pintype "bidirectional"))
      (node (ref "FLASH-SOCKET") (pin "P$9") (pinfunction "A20_P$9") (pintype "bidirectional"))
    )
    (net (code "26") (name "/A20_SRAM") (class "Default")
      (node (ref "CPLD") (pin "80") (pinfunction "IO80_80") (pintype "bidirectional"))
      (node (ref "SRAM") (pin "45") (pinfunction "A20_45") (pintype "bidirectional"))
    )
    (net (code "27") (name "/A21") (class "Default")
      (node (ref "CPLD") (pin "11") (pinfunction "IO11_11") (pintype "bidirectional"))
      (node (ref "PIO") (pin "62") (pinfunction "S_62") (pintype "passive"))
    )
    (net (code "28") (name "/A22") (class "Default")
      (node (ref "CPLD") (pin "12") (pinfunction "IO12_12") (pintype "bidirectional"))
      (node (ref "PIO") (pin "29") (pinfunction "S_29") (pintype "passive"))
    )
    (net (code "29") (name "/CLK") (class "Default")
      (node (ref "CH") (pin "13") (pinfunction "XI_13") (pintype "bidirectional"))
      (node (ref "CPLD") (pin "27") (pinfunction "IO27/GCK_27") (pintype "bidirectional"))
      (node (ref "FT2232H") (pin "2") (pinfunction "OSCI_2") (pintype "bidirectional"))
      (node (ref "U$2") (pin "P3") (pinfunction "OUTPUT_P3") (pintype "passive"))
    )
    (net (code "30") (name "/CS_LEDS") (class "Default")
      (node (ref "CPLD") (pin "40") (pinfunction "IO40_40") (pintype "bidirectional"))
      (node (ref "LEDS") (pin "11") (pinfunction "LE_11") (pintype "bidirectional"))
    )
    (net (code "31") (name "/D0") (class "Default")
      (node (ref "CH") (pin "15") (pinfunction "D0_15") (pintype "bidirectional"))
      (node (ref "CPLD") (pin "20") (pinfunction "IO20_20") (pintype "bidirectional"))
      (node (ref "FLASH") (pin "29") (pinfunction "D0_29") (pintype "bidirectional"))
      (node (ref "FLASH-SOCKET") (pin "P$29") (pinfunction "D0_P$29") (pintype "bidirectional"))
      (node (ref "FT2232H") (pin "38") (pinfunction "BDBUS0_38") (pintype "bidirectional"))
      (node (ref "J1") (pin "15") (pinfunction "15_15") (pintype "passive"))
      (node (ref "LEDS") (pin "2") (pinfunction "D0_2") (pintype "bidirectional"))
      (node (ref "SRAM") (pin "29") (pinfunction "D0_29") (pintype "bidirectional"))
      (node (ref "SWITCH") (pin "12") (pinfunction "Q7_12") (pintype "bidirectional"))
      (node (ref "U$1") (pin "P4") (pinfunction "P4_P4") (pintype "passive"))
    )
    (net (code "32") (name "/D1") (class "Default")
      (node (ref "CH") (pin "16") (pinfunction "D1_16") (pintype "bidirectional"))
      (node (ref "CPLD") (pin "19") (pinfunction "IO19_19") (pintype "bidirectional"))
      (node (ref "FLASH") (pin "31") (pinfunction "D1_31") (pintype "bidirectional"))
      (node (ref "FLASH-SOCKET") (pin "P$31") (pinfunction "D1_P$31") (pintype "bidirectional"))
      (node (ref "FT2232H") (pin "39") (pinfunction "BDBUS1_39") (pintype "bidirectional"))
      (node (ref "J1") (pin "13") (pinfunction "13_13") (pintype "passive"))
      (node (ref "LEDS") (pin "3") (pinfunction "D1_3") (pintype "bidirectional"))
      (node (ref "SRAM") (pin "31") (pinfunction "D1_31") (pintype "bidirectional"))
      (node (ref "SWITCH") (pin "13") (pinfunction "Q6_13") (pintype "bidirectional"))
      (node (ref "U$1") (pin "P6") (pinfunction "P6_P6") (pintype "passive"))
    )
    (net (code "33") (name "/D2") (class "Default")
      (node (ref "CH") (pin "17") (pinfunction "D2_17") (pintype "bidirectional"))
      (node (ref "CPLD") (pin "18") (pinfunction "IO18_18") (pintype "bidirectional"))
      (node (ref "FLASH") (pin "33") (pinfunction "D2_33") (pintype "bidirectional"))
      (node (ref "FLASH-SOCKET") (pin "P$33") (pinfunction "D2_P$33") (pintype "bidirectional"))
      (node (ref "FT2232H") (pin "40") (pinfunction "BDBUS2_40") (pintype "bidirectional"))
      (node (ref "J1") (pin "11") (pinfunction "11_11") (pintype "passive"))
      (node (ref "LEDS") (pin "4") (pinfunction "D2_4") (pintype "bidirectional"))
      (node (ref "SRAM") (pin "33") (pinfunction "D2_33") (pintype "bidirectional"))
      (node (ref "SWITCH") (pin "14") (pinfunction "Q5_14") (pintype "bidirectional"))
      (node (ref "U$1") (pin "P5") (pinfunction "P5_P5") (pintype "passive"))
    )
    (net (code "34") (name "/D3") (class "Default")
      (node (ref "CH") (pin "18") (pinfunction "D3_18") (pintype "bidirectional"))
      (node (ref "CPLD") (pin "17") (pinfunction "IO17_17") (pintype "bidirectional"))
      (node (ref "FLASH") (pin "35") (pinfunction "D3_35") (pintype "bidirectional"))
      (node (ref "FLASH-SOCKET") (pin "P$35") (pinfunction "D3_P$35") (pintype "bidirectional"))
      (node (ref "FT2232H") (pin "41") (pinfunction "BDBUS3_41") (pintype "bidirectional"))
      (node (ref "J1") (pin "9") (pinfunction "9_9") (pintype "passive"))
      (node (ref "LEDS") (pin "5") (pinfunction "D3_5") (pintype "bidirectional"))
      (node (ref "SRAM") (pin "35") (pinfunction "D3_35") (pintype "bidirectional"))
      (node (ref "SWITCH") (pin "15") (pinfunction "Q4_15") (pintype "bidirectional"))
      (node (ref "U$1") (pin "P7") (pinfunction "P7_P7") (pintype "passive"))
    )
    (net (code "35") (name "/D4") (class "Default")
      (node (ref "CH") (pin "19") (pinfunction "D4_19") (pintype "bidirectional"))
      (node (ref "CPLD") (pin "16") (pinfunction "IO16_16") (pintype "bidirectional"))
      (node (ref "FLASH") (pin "38") (pinfunction "D4_38") (pintype "bidirectional"))
      (node (ref "FLASH-SOCKET") (pin "P$38") (pinfunction "D4_P$38") (pintype "bidirectional"))
      (node (ref "FT2232H") (pin "21") (pinfunction "ADBUS4_21") (pintype "bidirectional"))
      (node (ref "FT2232H") (pin "43") (pinfunction "BDBUS4_43") (pintype "bidirectional"))
      (node (ref "J1") (pin "7") (pinfunction "7_7") (pintype "passive"))
      (node (ref "LEDS") (pin "6") (pinfunction "D4_6") (pintype "bidirectional"))
      (node (ref "SRAM") (pin "38") (pinfunction "D4_38") (pintype "bidirectional"))
      (node (ref "SWITCH") (pin "16") (pinfunction "Q3_16") (pintype "bidirectional"))
    )
    (net (code "36") (name "/D5") (class "Default")
      (node (ref "CH") (pin "20") (pinfunction "D5_20") (pintype "bidirectional"))
      (node (ref "CPLD") (pin "15") (pinfunction "IO15_15") (pintype "bidirectional"))
      (node (ref "FLASH") (pin "40") (pinfunction "D5_40") (pintype "bidirectional"))
      (node (ref "FLASH-SOCKET") (pin "P$40") (pinfunction "D5_P$40") (pintype "bidirectional"))
      (node (ref "FT2232H") (pin "22") (pinfunction "ADBUS5_22") (pintype "bidirectional"))
      (node (ref "FT2232H") (pin "44") (pinfunction "BDBUS5_44") (pintype "bidirectional"))
      (node (ref "J1") (pin "5") (pinfunction "5_5") (pintype "passive"))
      (node (ref "LEDS") (pin "7") (pinfunction "D5_7") (pintype "bidirectional"))
      (node (ref "SRAM") (pin "40") (pinfunction "D5_40") (pintype "bidirectional"))
      (node (ref "SWITCH") (pin "17") (pinfunction "Q2_17") (pintype "bidirectional"))
    )
    (net (code "37") (name "/D6") (class "Default")
      (node (ref "CH") (pin "21") (pinfunction "D6_21") (pintype "bidirectional"))
      (node (ref "CPLD") (pin "14") (pinfunction "IO14_14") (pintype "bidirectional"))
      (node (ref "FLASH") (pin "42") (pinfunction "D6_42") (pintype "bidirectional"))
      (node (ref "FLASH-SOCKET") (pin "P$42") (pinfunction "D6_P$42") (pintype "bidirectional"))
      (node (ref "FT2232H") (pin "23") (pinfunction "ADBUS6_23") (pintype "bidirectional"))
      (node (ref "FT2232H") (pin "45") (pinfunction "BDBUS6_45") (pintype "bidirectional"))
      (node (ref "J1") (pin "3") (pinfunction "3_3") (pintype "passive"))
      (node (ref "LEDS") (pin "8") (pinfunction "D6_8") (pintype "bidirectional"))
      (node (ref "SRAM") (pin "42") (pinfunction "D6_42") (pintype "bidirectional"))
      (node (ref "SWITCH") (pin "18") (pinfunction "Q1_18") (pintype "bidirectional"))
    )
    (net (code "38") (name "/D7") (class "Default")
      (node (ref "CH") (pin "22") (pinfunction "D7_22") (pintype "bidirectional"))
      (node (ref "CPLD") (pin "13") (pinfunction "IO13_13") (pintype "bidirectional"))
      (node (ref "FLASH") (pin "44") (pinfunction "D7_44") (pintype "bidirectional"))
      (node (ref "FLASH-SOCKET") (pin "P$44") (pinfunction "D7_P$44") (pintype "bidirectional"))
      (node (ref "FT2232H") (pin "24") (pinfunction "ADBUS7_24") (pintype "bidirectional"))
      (node (ref "FT2232H") (pin "46") (pinfunction "BDBUS7_46") (pintype "bidirectional"))
      (node (ref "J1") (pin "1") (pinfunction "1_1") (pintype "passive"))
      (node (ref "LEDS") (pin "9") (pinfunction "D7_9") (pintype "bidirectional"))
      (node (ref "SRAM") (pin "44") (pinfunction "D7_44") (pintype "bidirectional"))
      (node (ref "SWITCH") (pin "19") (pinfunction "Q0_19") (pintype "bidirectional"))
    )
    (net (code "39") (name "/DACK") (class "Default")
      (node (ref "CPLD") (pin "64") (pinfunction "IO64_64") (pintype "bidirectional"))
      (node (ref "PIO") (pin "36") (pinfunction "S_36") (pintype "passive"))
    )
    (net (code "40") (name "/DREQ") (class "Default")
      (node (ref "CPLD") (pin "71") (pinfunction "IO71_71") (pintype "bidirectional"))
      (node (ref "PIO") (pin "3") (pinfunction "S_3") (pintype "passive"))
    )
    (net (code "41") (name "/GPIO1") (class "Default")
      (node (ref "CPLD") (pin "74") (pinfunction "IO74_74") (pintype "bidirectional"))
      (node (ref "J2") (pin "1") (pinfunction "1_1") (pintype "passive"))
    )
    (net (code "42") (name "/GPIO2") (class "Default")
      (node (ref "CPLD") (pin "81") (pinfunction "IO81_81") (pintype "bidirectional"))
      (node (ref "J2") (pin "2") (pinfunction "2_2") (pintype "passive"))
    )
    (net (code "43") (name "/GPIO3") (class "Default")
      (node (ref "CPLD") (pin "73") (pinfunction "IO73_73") (pintype "bidirectional"))
      (node (ref "J2") (pin "3") (pinfunction "3_3") (pintype "passive"))
    )
    (net (code "44") (name "/GPIO4") (class "Default")
      (node (ref "CPLD") (pin "79") (pinfunction "IO79_79") (pintype "bidirectional"))
      (node (ref "J2") (pin "4") (pinfunction "4_4") (pintype "passive"))
    )
    (net (code "45") (name "/GPIO5") (class "Default")
      (node (ref "CPLD") (pin "68") (pinfunction "IO68_68") (pintype "bidirectional"))
      (node (ref "J2") (pin "5") (pinfunction "5_5") (pintype "passive"))
    )
    (net (code "46") (name "/GPIO6") (class "Default")
      (node (ref "CPLD") (pin "78") (pinfunction "IO78_78") (pintype "bidirectional"))
      (node (ref "J2") (pin "6") (pinfunction "6_6") (pintype "passive"))
    )
    (net (code "47") (name "/GPIO7") (class "Default")
      (node (ref "CPLD") (pin "63") (pinfunction "IO63_63") (pintype "bidirectional"))
      (node (ref "J2") (pin "7") (pinfunction "7_7") (pintype "passive"))
    )
    (net (code "48") (name "/GPIO8") (class "Default")
      (node (ref "CPLD") (pin "65") (pinfunction "IO65_65") (pintype "bidirectional"))
      (node (ref "J2") (pin "8") (pinfunction "8_8") (pintype "passive"))
    )
    (net (code "49") (name "/GPIO9") (class "Default")
      (node (ref "CPLD") (pin "58") (pinfunction "IO58_58") (pintype "bidirectional"))
      (node (ref "J2") (pin "9") (pinfunction "9_9") (pintype "passive"))
    )
    (net (code "50") (name "/GPIO10") (class "Default")
      (node (ref "CPLD") (pin "60") (pinfunction "IO60_60") (pintype "bidirectional"))
      (node (ref "J2") (pin "10") (pinfunction "10_10") (pintype "passive"))
    )
    (net (code "51") (name "/JP1") (class "Default")
      (node (ref "CPLD") (pin "35") (pinfunction "IO35_35") (pintype "bidirectional"))
      (node (ref "U$3") (pin "P$1") (pinfunction "P$1_P$1") (pintype "bidirectional"))
    )
    (net (code "52") (name "/JP2") (class "Default")
      (node (ref "CPLD") (pin "36") (pinfunction "IO36_36") (pintype "bidirectional"))
      (node (ref "U$4") (pin "P$1") (pinfunction "P$1_P$1") (pintype "bidirectional"))
    )
    (net (code "53") (name "/PD0") (class "Default")
      (node (ref "CPLD") (pin "89") (pinfunction "IO89_89") (pintype "bidirectional"))
      (node (ref "PIO") (pin "6") (pinfunction "S_6") (pintype "passive"))
    )
    (net (code "54") (name "/PD1") (class "Default")
      (node (ref "CPLD") (pin "90") (pinfunction "IO90_90") (pintype "bidirectional"))
      (node (ref "PIO") (pin "40") (pinfunction "S_40") (pintype "passive"))
    )
    (net (code "55") (name "/PD2") (class "Default")
      (node (ref "CPLD") (pin "91") (pinfunction "IO91_91") (pintype "bidirectional"))
      (node (ref "PIO") (pin "7") (pinfunction "S_7") (pintype "passive"))
    )
    (net (code "56") (name "/PD3") (class "Default")
      (node (ref "CPLD") (pin "92") (pinfunction "IO92_92") (pintype "bidirectional"))
      (node (ref "PIO") (pin "41") (pinfunction "S_41") (pintype "passive"))
    )
    (net (code "57") (name "/PD4") (class "Default")
      (node (ref "CPLD") (pin "93") (pinfunction "IO93_93") (pintype "bidirectional"))
      (node (ref "PIO") (pin "8") (pinfunction "S_8") (pintype "passive"))
    )
    (net (code "58") (name "/PD5") (class "Default")
      (node (ref "CPLD") (pin "94") (pinfunction "IO94_94") (pintype "bidirectional"))
      (node (ref "PIO") (pin "42") (pinfunction "S_42") (pintype "passive"))
    )
    (net (code "59") (name "/PD6") (class "Default")
      (node (ref "CPLD") (pin "95") (pinfunction "IO95_95") (pintype "bidirectional"))
      (node (ref "PIO") (pin "9") (pinfunction "S_9") (pintype "passive"))
    )
    (net (code "60") (name "/PD7") (class "Default")
      (node (ref "CPLD") (pin "96") (pinfunction "IO96_96") (pintype "bidirectional"))
      (node (ref "PIO") (pin "43") (pinfunction "S_43") (pintype "passive"))
    )
    (net (code "61") (name "/PORTA_A0") (class "Default")
      (node (ref "CPLD") (pin "54") (pinfunction "IO54_54") (pintype "bidirectional"))
      (node (ref "FT2232H") (pin "27") (pinfunction "ACBUS1_27") (pintype "bidirectional"))
    )
    (net (code "62") (name "/PVCC") (class "Default")
      (node (ref "D3") (pin "A") (pinfunction "A_A") (pintype "passive"))
      (node (ref "PIO") (pin "17") (pinfunction "S_17") (pintype "passive"))
      (node (ref "PIO") (pin "51") (pinfunction "S_51") (pintype "passive"))
    )
    (net (code "63") (name "/SBEN") (class "Default")
      (node (ref "CPLD") (pin "85") (pinfunction "IO85_85") (pintype "bidirectional"))
      (node (ref "R1") (pin "1") (pinfunction "1_1") (pintype "passive"))
    )
    (net (code "64") (name "/SOFT") (class "Default")
      (node (ref "CPLD") (pin "50") (pinfunction "IO50_50") (pintype "bidirectional"))
      (node (ref "S2") (pin "1") (pinfunction "1_1") (pintype "passive"))
    )
    (net (code "65") (name "/SW1") (class "Default")
      (node (ref "CPLD") (pin "76") (pinfunction "IO76_76") (pintype "bidirectional"))
      (node (ref "SW1") (pin "1-1") (pinfunction "1-1_1-1") (pintype "passive"))
    )
    (net (code "66") (name "/SW2") (class "Default")
      (node (ref "CPLD") (pin "77") (pinfunction "IO77_77") (pintype "bidirectional"))
      (node (ref "SW1") (pin "2-1") (pinfunction "2-1_2-1") (pintype "passive"))
    )
    (net (code "67") (name "/TCK") (class "Default")
      (node (ref "CPLD") (pin "48") (pinfunction "TCK_48") (pintype "bidirectional"))
      (node (ref "R25") (pin "1") (pinfunction "1_1") (pintype "passive"))
      (node (ref "U$1") (pin "TCK") (pinfunction "TCK_TCK") (pintype "passive"))
    )
    (net (code "68") (name "/TDI") (class "Default")
      (node (ref "CPLD") (pin "45") (pinfunction "TDI_45") (pintype "bidirectional"))
      (node (ref "R26") (pin "1") (pinfunction "1_1") (pintype "passive"))
      (node (ref "U$1") (pin "TDI") (pinfunction "TDI_TDI") (pintype "passive"))
    )
    (net (code "69") (name "/TDO") (class "Default")
      (node (ref "CPLD") (pin "83") (pinfunction "TDO_83") (pintype "bidirectional"))
      (node (ref "U$1") (pin "TDO") (pinfunction "TDO_TDO") (pintype "passive"))
    )
    (net (code "70") (name "/TMS") (class "Default")
      (node (ref "CPLD") (pin "47") (pinfunction "TMS_47") (pintype "bidirectional"))
      (node (ref "R27") (pin "1") (pinfunction "1_1") (pintype "passive"))
      (node (ref "U$1") (pin "TMS") (pinfunction "TMS_TMS") (pintype "passive"))
    )
    (net (code "71") (name "/~{CS0}") (class "Default")
      (node (ref "CPLD") (pin "86") (pinfunction "IO86_86") (pintype "bidirectional"))
      (node (ref "PIO") (pin "4") (pinfunction "S_4") (pintype "passive"))
    )
    (net (code "72") (name "/~{CS2}") (class "Default")
      (node (ref "CPLD") (pin "87") (pinfunction "IO87_87") (pintype "bidirectional"))
      (node (ref "PIO") (pin "39") (pinfunction "S_39") (pintype "passive"))
    )
    (net (code "73") (name "/~{CS_CH}") (class "Default")
      (node (ref "CH") (pin "27") (pinfunction "~{CS}_27") (pintype "bidirectional"))
      (node (ref "CPLD") (pin "37") (pinfunction "IO37_37") (pintype "bidirectional"))
    )
    (net (code "74") (name "/~{CS_FLASH}") (class "Default")
      (node (ref "CPLD") (pin "29") (pinfunction "IO29_29") (pintype "bidirectional"))
      (node (ref "FLASH") (pin "26") (pinfunction "~{CE}_26") (pintype "input"))
    )
    (net (code "75") (name "/~{CS_PORTA}") (class "Default")
      (node (ref "CPLD") (pin "55") (pinfunction "IO55_55") (pintype "bidirectional"))
      (node (ref "FT2232H") (pin "26") (pinfunction "ACBUS0_26") (pintype "bidirectional"))
    )
    (net (code "76") (name "/~{CS_PORTB}") (class "Default")
      (node (ref "CPLD") (pin "53") (pinfunction "IO53_53") (pintype "bidirectional"))
      (node (ref "FT2232H") (pin "48") (pinfunction "BCBUS0_48") (pintype "bidirectional"))
    )
    (net (code "77") (name "/~{CS_SOCKET}") (class "Default")
      (node (ref "CPLD") (pin "34") (pinfunction "IO34_34") (pintype "bidirectional"))
      (node (ref "FLASH-SOCKET") (pin "P$26") (pinfunction "~{CE}_P$26") (pintype "input"))
    )
    (net (code "78") (name "/~{CS_SRAM}") (class "Default")
      (node (ref "CPLD") (pin "24") (pinfunction "IO24_24") (pintype "bidirectional"))
      (node (ref "SRAM") (pin "26") (pinfunction "~{CE1}_26") (pintype "bidirectional"))
    )
    (net (code "79") (name "/~{CS_SWITCH}") (class "Default")
      (node (ref "CPLD") (pin "25") (pinfunction "IO25_25") (pintype "bidirectional"))
      (node (ref "SWITCH") (pin "1") (pinfunction "~{OE}_1") (pintype "bidirectional"))
    )
    (net (code "80") (name "/~{IN10}") (class "Default")
      (node (ref "CPLD") (pin "82") (pinfunction "IO82_82") (pintype "bidirectional"))
      (node (ref "PIO") (pin "37") (pinfunction "S_37") (pintype "passive"))
    )
    (net (code "81") (name "/~{IN_CH}") (class "Default")
      (node (ref "CH") (pin "1") (pinfunction "~{INT}_1") (pintype "bidirectional"))
      (node (ref "CPLD") (pin "39") (pinfunction "IO39_39") (pintype "bidirectional"))
    )
    (net (code "82") (name "/~{RD}") (class "Default")
      (node (ref "CH") (pin "4") (pinfunction "~{RD}_4") (pintype "bidirectional"))
      (node (ref "CPLD") (pin "23") (pinfunction "IO23/GCK_23") (pintype "bidirectional"))
      (node (ref "FLASH") (pin "28") (pinfunction "~{OE}_28") (pintype "input"))
      (node (ref "FLASH-SOCKET") (pin "P$28") (pinfunction "~{OE}_P$28") (pintype "input"))
      (node (ref "FT2232H") (pin "28") (pinfunction "ACBUS2_28") (pintype "bidirectional"))
      (node (ref "FT2232H") (pin "53") (pinfunction "BCBUS2_53") (pintype "bidirectional"))
      (node (ref "PIO") (pin "30") (pinfunction "S_30") (pintype "passive"))
      (node (ref "SRAM") (pin "28") (pinfunction "~{OE}_28") (pintype "bidirectional"))
    )
    (net (code "83") (name "/~{RESET_FT}") (class "Default")
      (node (ref "CPLD") (pin "56") (pinfunction "IO56_56") (pintype "bidirectional"))
      (node (ref "FT2232H") (pin "14") (pinfunction "RESET#_14") (pintype "bidirectional"))
      (node (ref "R15") (pin "1") (pinfunction "1_1") (pintype "passive"))
      (node (ref "R16") (pin "2") (pinfunction "2_2") (pintype "passive"))
    )
    (net (code "84") (name "/~{RESET}") (class "Default")
      (node (ref "CH") (pin "2") (pinfunction "RSTI_2") (pintype "bidirectional"))
      (node (ref "CPLD") (pin "99") (pinfunction "IO99/GSR_99") (pintype "bidirectional"))
      (node (ref "FLASH") (pin "12") (pinfunction "~{RESET}_12") (pintype "bidirectional"))
      (node (ref "FLASH-SOCKET") (pin "P$12") (pinfunction "~{RESET}_P$12") (pintype "bidirectional"))
      (node (ref "PIO") (pin "2") (pinfunction "S_2") (pintype "passive"))
    )
    (net (code "85") (name "/~{WR2}") (class "Default")
      (node (ref "CPLD") (pin "66") (pinfunction "IO66_66") (pintype "bidirectional"))
      (node (ref "PIO") (pin "38") (pinfunction "S_38") (pintype "passive"))
    )
    (net (code "86") (name "/~{WR}") (class "Default")
      (node (ref "CH") (pin "3") (pinfunction "~{WR}_3") (pintype "bidirectional"))
      (node (ref "CPLD") (pin "22") (pinfunction "IO22/GCK_22") (pintype "bidirectional"))
      (node (ref "FLASH") (pin "11") (pinfunction "~{WE}_11") (pintype "input"))
      (node (ref "FLASH-SOCKET") (pin "P$11") (pinfunction "~{WE}_P$11") (pintype "input"))
      (node (ref "FT2232H") (pin "29") (pinfunction "ACBUS3_29") (pintype "bidirectional"))
      (node (ref "FT2232H") (pin "54") (pinfunction "BCBUS3_54") (pintype "bidirectional"))
      (node (ref "PIO") (pin "64") (pinfunction "S_64") (pintype "passive"))
      (node (ref "SRAM") (pin "11") (pinfunction "~{WE}_11") (pintype "bidirectional"))
    )
    (net (code "87") (name "GND") (class "Default")
      (node (ref "C1") (pin "2") (pinfunction "2_2") (pintype "passive"))
      (node (ref "C10") (pin "2") (pinfunction "2_2") (pintype "passive"))
      (node (ref "C11") (pin "2") (pinfunction "2_2") (pintype "passive"))
      (node (ref "C12") (pin "2") (pinfunction "2_2") (pintype "passive"))
      (node (ref "C13") (pin "2") (pinfunction "2_2") (pintype "passive"))
      (node (ref "C14") (pin "2") (pinfunction "2_2") (pintype "passive"))
      (node (ref "C15") (pin "2") (pinfunction "2_2") (pintype "passive"))
      (node (ref "C16") (pin "2") (pinfunction "2_2") (pintype "passive"))
      (node (ref "C17") (pin "2") (pinfunction "2_2") (pintype "passive"))
      (node (ref "C18") (pin "2") (pinfunction "2_2") (pintype "passive"))
      (node (ref "C19") (pin "2") (pinfunction "2_2") (pintype "passive"))
      (node (ref "C2") (pin "2") (pinfunction "2_2") (pintype "passive"))
      (node (ref "C20") (pin "2") (pinfunction "2_2") (pintype "passive"))
      (node (ref "C21") (pin "-") (pinfunction "-_-") (pintype "passive"))
      (node (ref "C22") (pin "2") (pinfunction "2_2") (pintype "passive"))
      (node (ref "C23") (pin "2") (pinfunction "2_2") (pintype "passive"))
      (node (ref "C24") (pin "2") (pinfunction "2_2") (pintype "passive"))
      (node (ref "C25") (pin "2") (pinfunction "2_2") (pintype "passive"))
      (node (ref "C26") (pin "-") (pinfunction "-_-") (pintype "passive"))
      (node (ref "C27") (pin "-") (pinfunction "-_-") (pintype "passive"))
      (node (ref "C28") (pin "2") (pinfunction "2_2") (pintype "passive"))
      (node (ref "C29") (pin "2") (pinfunction "2_2") (pintype "passive"))
      (node (ref "C3") (pin "2") (pinfunction "2_2") (pintype "passive"))
      (node (ref "C30") (pin "2") (pinfunction "2_2") (pintype "passive"))
      (node (ref "C4") (pin "2") (pinfunction "2_2") (pintype "passive"))
      (node (ref "C5") (pin "2") (pinfunction "2_2") (pintype "passive"))
      (node (ref "C6") (pin "2") (pinfunction "2_2") (pintype "passive"))
      (node (ref "C7") (pin "2") (pinfunction "2_2") (pintype "passive"))
      (node (ref "C8") (pin "-") (pinfunction "-_-") (pintype "passive"))
      (node (ref "C9") (pin "2") (pinfunction "2_2") (pintype "passive"))
      (node (ref "CH") (pin "12") (pinfunction "GND1_12") (pintype "bidirectional"))
      (node (ref "CH") (pin "23") (pinfunction "GND2_23") (pintype "bidirectional"))
      (node (ref "CH") (pin "5") (pinfunction "TX_5") (pintype "bidirectional"))
      (node (ref "CPLD") (pin "100") (pinfunction "GND_100") (pintype "bidirectional"))
      (node (ref "CPLD") (pin "21") (pinfunction "GND_21") (pintype "bidirectional"))
      (node (ref "CPLD") (pin "31") (pinfunction "GND_31") (pintype "bidirectional"))
      (node (ref "CPLD") (pin "44") (pinfunction "GND_44") (pintype "bidirectional"))
      (node (ref "CPLD") (pin "62") (pinfunction "GND_62") (pintype "bidirectional"))
      (node (ref "CPLD") (pin "69") (pinfunction "GND_69") (pintype "bidirectional"))
      (node (ref "CPLD") (pin "75") (pinfunction "GND_75") (pintype "bidirectional"))
      (node (ref "CPLD") (pin "84") (pinfunction "GND_84") (pintype "bidirectional"))
      (node (ref "D1") (pin "2") (pinfunction "2_2") (pintype "passive"))
      (node (ref "D2") (pin "2") (pinfunction "2_2") (pintype "passive"))
      (node (ref "EEPROM") (pin "2") (pinfunction "GND_2") (pintype "power_in"))
      (node (ref "FLASH") (pin "27") (pinfunction "GND_27") (pintype "power_in"))
      (node (ref "FLASH") (pin "46") (pinfunction "GND_46") (pintype "power_in"))
      (node (ref "FLASH") (pin "47") (pinfunction "~{BYTE}_47") (pintype "bidirectional"))
      (node (ref "FLASH-SOCKET") (pin "P$27") (pinfunction "GND_P$27") (pintype "power_in"))
      (node (ref "FLASH-SOCKET") (pin "P$46") (pinfunction "GND_P$46") (pintype "power_in"))
      (node (ref "FLASH-SOCKET") (pin "P$47") (pinfunction "~{BYTE}_P$47") (pintype "bidirectional"))
      (node (ref "FT2232H") (pin "1") (pinfunction "GND_1") (pintype "bidirectional"))
      (node (ref "FT2232H") (pin "10") (pinfunction "AGND_10") (pintype "bidirectional"))
      (node (ref "FT2232H") (pin "11") (pinfunction "GND_11") (pintype "bidirectional"))
      (node (ref "FT2232H") (pin "13") (pinfunction "TEST_13") (pintype "bidirectional"))
      (node (ref "FT2232H") (pin "15") (pinfunction "GND_15") (pintype "bidirectional"))
      (node (ref "FT2232H") (pin "25") (pinfunction "GND_25") (pintype "bidirectional"))
      (node (ref "FT2232H") (pin "35") (pinfunction "GND_35") (pintype "bidirectional"))
      (node (ref "FT2232H") (pin "47") (pinfunction "GND_47") (pintype "bidirectional"))
      (node (ref "FT2232H") (pin "5") (pinfunction "GND_5") (pintype "bidirectional"))
      (node (ref "FT2232H") (pin "51") (pinfunction "GND_51") (pintype "bidirectional"))
      (node (ref "IC2") (pin "1") (pinfunction "ADJ_1") (pintype "input"))
      (node (ref "J1") (pin "10") (pinfunction "10_10") (pintype "passive"))
      (node (ref "J1") (pin "12") (pinfunction "12_12") (pintype "passive"))
      (node (ref "J1") (pin "14") (pinfunction "14_14") (pintype "passive"))
      (node (ref "J1") (pin "16") (pinfunction "16_16") (pintype "passive"))
      (node (ref "J1") (pin "2") (pinfunction "2_2") (pintype "passive"))
      (node (ref "J1") (pin "4") (pinfunction "4_4") (pintype "passive"))
      (node (ref "J1") (pin "6") (pinfunction "6_6") (pintype "passive"))
      (node (ref "J1") (pin "8") (pinfunction "8_8") (pintype "passive"))
      (node (ref "J3") (pin "GND") (pinfunction "GND_GND") (pintype "power_in"))
      (node (ref "J3") (pin "SHLD1") (pinfunction "SHIELD_SHLD1") (pintype "bidirectional"))
      (node (ref "J3") (pin "SHLD2") (pinfunction "SHIELD_SHLD2") (pintype "bidirectional"))
      (node (ref "JP1") (pin "3") (pinfunction "3_3") (pintype "passive"))
      (node (ref "JP1") (pin "4") (pinfunction "4_4") (pintype "passive"))
      (node (ref "LEDS") (pin "1") (pinfunction "~{OE}_1") (pintype "bidirectional"))
      (node (ref "LEDS") (pin "10") (pinfunction "GND_10") (pintype "bidirectional"))
      (node (ref "PIO") (pin "1") (pinfunction "S_1") (pintype "passive"))
      (node (ref "PIO") (pin "16") (pinfunction "S_16") (pintype "passive"))
      (node (ref "PIO") (pin "19") (pinfunction "S_19") (pintype "passive"))
      (node (ref "PIO") (pin "34") (pinfunction "S_34") (pintype "passive"))
      (node (ref "PIO") (pin "35") (pinfunction "S_35") (pintype "passive"))
      (node (ref "PIO") (pin "50") (pinfunction "S_50") (pintype "passive"))
      (node (ref "PIO") (pin "53") (pinfunction "S_53") (pintype "passive"))
      (node (ref "PIO") (pin "68") (pinfunction "S_68") (pintype "passive"))
      (node (ref "R14") (pin "1") (pinfunction "1_1") (pintype "passive"))
      (node (ref "R16") (pin "1") (pinfunction "1_1") (pintype "passive"))
      (node (ref "S1") (pin "1") (pinfunction "1_1") (pintype "passive"))
      (node (ref "S1") (pin "2") (pinfunction "2_2") (pintype "passive"))
      (node (ref "S1") (pin "3") (pinfunction "3_3") (pintype "passive"))
      (node (ref "S1") (pin "4") (pinfunction "4_4") (pintype "passive"))
      (node (ref "S1") (pin "5") (pinfunction "5_5") (pintype "passive"))
      (node (ref "S1") (pin "6") (pinfunction "6_6") (pintype "passive"))
      (node (ref "S1") (pin "7") (pinfunction "7_7") (pintype "passive"))
      (node (ref "S1") (pin "8") (pinfunction "8_8") (pintype "passive"))
      (node (ref "S2") (pin "2") (pinfunction "2_2") (pintype "passive"))
      (node (ref "SRAM") (pin "27") (pinfunction "GND_27") (pintype "bidirectional"))
      (node (ref "SRAM") (pin "46") (pinfunction "GND_46") (pintype "bidirectional"))
      (node (ref "SRAM") (pin "47") (pinfunction "GND_47") (pintype "bidirectional"))
      (node (ref "SW1") (pin "1") (pinfunction "1_1") (pintype "passive"))
      (node (ref "SW1") (pin "2") (pinfunction "2_2") (pintype "passive"))
      (node (ref "SWITCH") (pin "10") (pinfunction "GND_10") (pintype "bidirectional"))
      (node (ref "U$1") (pin "GND") (pinfunction "GND_GND") (pintype "passive"))
      (node (ref "U$2") (pin "P2") (pinfunction "GND_P2") (pintype "passive"))
      (node (ref "U$3") (pin "P$2") (pinfunction "P$2_P$2") (pintype "bidirectional"))
      (node (ref "U$4") (pin "P$2") (pinfunction "P$2_P$2") (pintype "bidirectional"))
      (node (ref "X1") (pin "5") (pinfunction "5_5") (pintype "input"))
    )
    (net (code "88") (name "Net-(C24-Pad1)") (class "Default")
      (node (ref "C24") (pin "1") (pinfunction "1_1") (pintype "passive"))
      (node (ref "FB3") (pin "2") (pinfunction "2_2") (pintype "passive"))
      (node (ref "R15") (pin "2") (pinfunction "2_2") (pintype "passive"))
    )
    (net (code "89") (name "Net-(CH-UD+)") (class "Default")
      (node (ref "CH") (pin "10") (pinfunction "UD+_10") (pintype "bidirectional"))
      (node (ref "J3") (pin "D+") (pinfunction "D+_D+") (pintype "bidirectional"))
    )
    (net (code "90") (name "Net-(CH-UD-)") (class "Default")
      (node (ref "CH") (pin "11") (pinfunction "UD-_11") (pintype "bidirectional"))
      (node (ref "J3") (pin "D-") (pinfunction "D-_D-") (pintype "bidirectional"))
    )
    (net (code "91") (name "Net-(CH-V3)") (class "Default")
      (node (ref "C29") (pin "1") (pinfunction "1_1") (pintype "passive"))
      (node (ref "CH") (pin "9") (pinfunction "V3_9") (pintype "bidirectional"))
    )
    (net (code "92") (name "Net-(D1-Pad1)") (class "Default")
      (node (ref "D1") (pin "1") (pinfunction "1_1") (pintype "passive"))
      (node (ref "R13") (pin "1") (pinfunction "1_1") (pintype "passive"))
      (node (ref "X1") (pin "3") (pinfunction "3_3") (pintype "input"))
    )
    (net (code "93") (name "Net-(D2-Pad1)") (class "Default")
      (node (ref "D2") (pin "1") (pinfunction "1_1") (pintype "passive"))
      (node (ref "R12") (pin "1") (pinfunction "1_1") (pintype "passive"))
      (node (ref "X1") (pin "2") (pinfunction "2_2") (pintype "input"))
    )
    (net (code "94") (name "Net-(EEPROM-CLK)") (class "Default")
      (node (ref "EEPROM") (pin "4") (pinfunction "CLK_4") (pintype "input"))
      (node (ref "FT2232H") (pin "62") (pinfunction "EECLK_62") (pintype "bidirectional"))
    )
    (net (code "95") (name "Net-(EEPROM-CS)") (class "Default")
      (node (ref "EEPROM") (pin "5") (pinfunction "CS_5") (pintype "input"))
      (node (ref "FT2232H") (pin "63") (pinfunction "EECS_63") (pintype "bidirectional"))
    )
    (net (code "96") (name "Net-(EEPROM-DI)") (class "Default")
      (node (ref "EEPROM") (pin "3") (pinfunction "DI_3") (pintype "input"))
      (node (ref "FT2232H") (pin "61") (pinfunction "EEDATA_61") (pintype "bidirectional"))
      (node (ref "R11") (pin "2") (pinfunction "2_2") (pintype "passive"))
    )
    (net (code "97") (name "Net-(EEPROM-DO)") (class "Default")
      (node (ref "EEPROM") (pin "1") (pinfunction "DO_1") (pintype "tri_state"))
      (node (ref "R10") (pin "1") (pinfunction "1_1") (pintype "passive"))
      (node (ref "R11") (pin "1") (pinfunction "1_1") (pintype "passive"))
    )
    (net (code "98") (name "Net-(FB3-Pad1)") (class "Default")
      (node (ref "FB3") (pin "1") (pinfunction "1_1") (pintype "passive"))
      (node (ref "X1") (pin "1") (pinfunction "1_1") (pintype "input"))
    )
    (net (code "99") (name "Net-(FT2232H-ADBUS0)") (class "Default")
      (node (ref "FT2232H") (pin "16") (pinfunction "ADBUS0_16") (pintype "bidirectional"))
      (node (ref "U$1") (pin "P3") (pinfunction "P3_P3") (pintype "passive"))
    )
    (net (code "100") (name "Net-(FT2232H-ADBUS1)") (class "Default")
      (node (ref "FT2232H") (pin "17") (pinfunction "ADBUS1_17") (pintype "bidirectional"))
      (node (ref "U$1") (pin "P1") (pinfunction "P1_P1") (pintype "passive"))
    )
    (net (code "101") (name "Net-(FT2232H-ADBUS2)") (class "Default")
      (node (ref "FT2232H") (pin "18") (pinfunction "ADBUS2_18") (pintype "bidirectional"))
      (node (ref "U$1") (pin "P2") (pinfunction "P2_P2") (pintype "passive"))
    )
    (net (code "102") (name "Net-(FT2232H-ADBUS3)") (class "Default")
      (node (ref "FT2232H") (pin "19") (pinfunction "ADBUS3_19") (pintype "bidirectional"))
      (node (ref "U$1") (pin "P0") (pinfunction "P0_P0") (pintype "passive"))
    )
    (net (code "103") (name "Net-(FT2232H-D+)") (class "Default")
      (node (ref "FT2232H") (pin "8") (pinfunction "D+_8") (pintype "bidirectional"))
      (node (ref "R13") (pin "2") (pinfunction "2_2") (pintype "passive"))
    )
    (net (code "104") (name "Net-(FT2232H-D-)") (class "Default")
      (node (ref "FT2232H") (pin "7") (pinfunction "D-_7") (pintype "bidirectional"))
      (node (ref "R12") (pin "2") (pinfunction "2_2") (pintype "passive"))
    )
    (net (code "105") (name "Net-(FT2232H-REF)") (class "Default")
      (node (ref "FT2232H") (pin "6") (pinfunction "REF_6") (pintype "bidirectional"))
      (node (ref "R14") (pin "2") (pinfunction "2_2") (pintype "passive"))
    )
    (net (code "106") (name "Net-(FT2232H-VPHY)") (class "Default")
      (node (ref "C23") (pin "1") (pinfunction "1_1") (pintype "passive"))
      (node (ref "FB2") (pin "2") (pinfunction "2_2") (pintype "passive"))
      (node (ref "FT2232H") (pin "4") (pinfunction "VPHY_4") (pintype "bidirectional"))
    )
    (net (code "107") (name "Net-(FT2232H-VPLL)") (class "Default")
      (node (ref "C22") (pin "1") (pinfunction "1_1") (pintype "passive"))
      (node (ref "FB1") (pin "2") (pinfunction "2_2") (pintype "passive"))
      (node (ref "FT2232H") (pin "9") (pinfunction "VPLL_9") (pintype "bidirectional"))
    )
    (net (code "108") (name "Net-(FT2232H-VREGOUT)") (class "Default")
      (node (ref "C12") (pin "1") (pinfunction "1_1") (pintype "passive"))
      (node (ref "C13") (pin "1") (pinfunction "1_1") (pintype "passive"))
      (node (ref "C14") (pin "1") (pinfunction "1_1") (pintype "passive"))
      (node (ref "C19") (pin "1") (pinfunction "1_1") (pintype "passive"))
      (node (ref "C21") (pin "+") (pinfunction "+_+") (pintype "passive"))
      (node (ref "FT2232H") (pin "12") (pinfunction "VCORE_12") (pintype "bidirectional"))
      (node (ref "FT2232H") (pin "37") (pinfunction "VCORE_37") (pintype "bidirectional"))
      (node (ref "FT2232H") (pin "49") (pinfunction "VREGOUT_49") (pintype "bidirectional"))
      (node (ref "FT2232H") (pin "64") (pinfunction "VCORE_64") (pintype "bidirectional"))
    )
    (net (code "109") (name "Net-(LED1-PadC)") (class "Default")
      (node (ref "LED1") (pin "C") (pinfunction "C_C") (pintype "passive"))
      (node (ref "R24") (pin "1") (pinfunction "1_1") (pintype "passive"))
    )
    (net (code "110") (name "Net-(LED2-PadC)") (class "Default")
      (node (ref "LED2") (pin "C") (pinfunction "C_C") (pintype "passive"))
      (node (ref "R23") (pin "1") (pinfunction "1_1") (pintype "passive"))
    )
    (net (code "111") (name "Net-(LED3-PadC)") (class "Default")
      (node (ref "LED3") (pin "C") (pinfunction "C_C") (pintype "passive"))
      (node (ref "R22") (pin "1") (pinfunction "1_1") (pintype "passive"))
    )
    (net (code "112") (name "Net-(LED4-PadC)") (class "Default")
      (node (ref "LED4") (pin "C") (pinfunction "C_C") (pintype "passive"))
      (node (ref "R21") (pin "1") (pinfunction "1_1") (pintype "passive"))
    )
    (net (code "113") (name "Net-(LED5-PadC)") (class "Default")
      (node (ref "LED5") (pin "C") (pinfunction "C_C") (pintype "passive"))
      (node (ref "R20") (pin "1") (pinfunction "1_1") (pintype "passive"))
    )
    (net (code "114") (name "Net-(LED6-PadC)") (class "Default")
      (node (ref "LED6") (pin "C") (pinfunction "C_C") (pintype "passive"))
      (node (ref "R19") (pin "1") (pinfunction "1_1") (pintype "passive"))
    )
    (net (code "115") (name "Net-(LED7-PadC)") (class "Default")
      (node (ref "LED7") (pin "C") (pinfunction "C_C") (pintype "passive"))
      (node (ref "R18") (pin "1") (pinfunction "1_1") (pintype "passive"))
    )
    (net (code "116") (name "Net-(LED8-PadC)") (class "Default")
      (node (ref "LED8") (pin "C") (pinfunction "C_C") (pintype "passive"))
      (node (ref "R17") (pin "1") (pinfunction "1_1") (pintype "passive"))
    )
    (net (code "117") (name "Net-(LEDS-Q0)") (class "Default")
      (node (ref "LEDS") (pin "19") (pinfunction "Q0_19") (pintype "bidirectional"))
      (node (ref "R24") (pin "2") (pinfunction "2_2") (pintype "passive"))
    )
    (net (code "118") (name "Net-(LEDS-Q1)") (class "Default")
      (node (ref "LEDS") (pin "18") (pinfunction "Q1_18") (pintype "bidirectional"))
      (node (ref "R23") (pin "2") (pinfunction "2_2") (pintype "passive"))
    )
    (net (code "119") (name "Net-(LEDS-Q2)") (class "Default")
      (node (ref "LEDS") (pin "17") (pinfunction "Q2_17") (pintype "bidirectional"))
      (node (ref "R22") (pin "2") (pinfunction "2_2") (pintype "passive"))
    )
    (net (code "120") (name "Net-(LEDS-Q3)") (class "Default")
      (node (ref "LEDS") (pin "16") (pinfunction "Q3_16") (pintype "bidirectional"))
      (node (ref "R21") (pin "2") (pinfunction "2_2") (pintype "passive"))
    )
    (net (code "121") (name "Net-(LEDS-Q4)") (class "Default")
      (node (ref "LEDS") (pin "15") (pinfunction "Q4_15") (pintype "bidirectional"))
      (node (ref "R20") (pin "2") (pinfunction "2_2") (pintype "passive"))
    )
    (net (code "122") (name "Net-(LEDS-Q5)") (class "Default")
      (node (ref "LEDS") (pin "14") (pinfunction "Q5_14") (pintype "bidirectional"))
      (node (ref "R19") (pin "2") (pinfunction "2_2") (pintype "passive"))
    )
    (net (code "123") (name "Net-(LEDS-Q6)") (class "Default")
      (node (ref "LEDS") (pin "13") (pinfunction "Q6_13") (pintype "bidirectional"))
      (node (ref "R18") (pin "2") (pinfunction "2_2") (pintype "passive"))
    )
    (net (code "124") (name "Net-(LEDS-Q7)") (class "Default")
      (node (ref "LEDS") (pin "12") (pinfunction "Q7_12") (pintype "bidirectional"))
      (node (ref "R17") (pin "2") (pinfunction "2_2") (pintype "passive"))
    )
    (net (code "125") (name "Net-(PIOBK-S)") (class "Default")
      (node (ref "PIO") (pin "5") (pinfunction "S_5") (pintype "passive"))
      (node (ref "R1") (pin "2") (pinfunction "2_2") (pintype "passive"))
    )
    (net (code "126") (name "Net-(SWITCH-D0)") (class "Default")
      (node (ref "R9") (pin "1") (pinfunction "1_1") (pintype "passive"))
      (node (ref "S1") (pin "16") (pinfunction "16_16") (pintype "passive"))
      (node (ref "SWITCH") (pin "2") (pinfunction "D0_2") (pintype "bidirectional"))
    )
    (net (code "127") (name "Net-(SWITCH-D1)") (class "Default")
      (node (ref "R8") (pin "1") (pinfunction "1_1") (pintype "passive"))
      (node (ref "S1") (pin "15") (pinfunction "15_15") (pintype "passive"))
      (node (ref "SWITCH") (pin "3") (pinfunction "D1_3") (pintype "bidirectional"))
    )
    (net (code "128") (name "Net-(SWITCH-D2)") (class "Default")
      (node (ref "R7") (pin "1") (pinfunction "1_1") (pintype "passive"))
      (node (ref "S1") (pin "14") (pinfunction "14_14") (pintype "passive"))
      (node (ref "SWITCH") (pin "4") (pinfunction "D2_4") (pintype "bidirectional"))
    )
    (net (code "129") (name "Net-(SWITCH-D3)") (class "Default")
      (node (ref "R6") (pin "1") (pinfunction "1_1") (pintype "passive"))
      (node (ref "S1") (pin "13") (pinfunction "13_13") (pintype "passive"))
      (node (ref "SWITCH") (pin "5") (pinfunction "D3_5") (pintype "bidirectional"))
    )
    (net (code "130") (name "Net-(SWITCH-D4)") (class "Default")
      (node (ref "R5") (pin "1") (pinfunction "1_1") (pintype "passive"))
      (node (ref "S1") (pin "12") (pinfunction "12_12") (pintype "passive"))
      (node (ref "SWITCH") (pin "6") (pinfunction "D4_6") (pintype "bidirectional"))
    )
    (net (code "131") (name "Net-(SWITCH-D5)") (class "Default")
      (node (ref "R4") (pin "1") (pinfunction "1_1") (pintype "passive"))
      (node (ref "S1") (pin "11") (pinfunction "11_11") (pintype "passive"))
      (node (ref "SWITCH") (pin "7") (pinfunction "D5_7") (pintype "bidirectional"))
    )
    (net (code "132") (name "Net-(SWITCH-D6)") (class "Default")
      (node (ref "R3") (pin "1") (pinfunction "1_1") (pintype "passive"))
      (node (ref "S1") (pin "10") (pinfunction "10_10") (pintype "passive"))
      (node (ref "SWITCH") (pin "8") (pinfunction "D6_8") (pintype "bidirectional"))
    )
    (net (code "133") (name "Net-(SWITCH-D7)") (class "Default")
      (node (ref "R2") (pin "1") (pinfunction "1_1") (pintype "passive"))
      (node (ref "S1") (pin "9") (pinfunction "9_9") (pintype "passive"))
      (node (ref "SWITCH") (pin "9") (pinfunction "D7_9") (pintype "bidirectional"))
    )
    (net (code "134") (name "V+") (class "Default")
      (node (ref "C26") (pin "+") (pinfunction "+_+") (pintype "passive"))
      (node (ref "C28") (pin "1") (pinfunction "1_1") (pintype "passive"))
      (node (ref "IC2") (pin "3") (pinfunction "IN_3") (pintype "input"))
      (node (ref "PIO") (pin "18") (pinfunction "S_18") (pintype "passive"))
      (node (ref "PIO") (pin "52") (pinfunction "S_52") (pintype "passive"))
    )
    (net (code "135") (name "unconnected-(CH-RST-Pad25)") (class "Default")
      (node (ref "CH") (pin "25") (pinfunction "RST_25") (pintype "bidirectional"))
    )
    (net (code "136") (name "unconnected-(CH-RX-Pad6)") (class "Default")
      (node (ref "CH") (pin "6") (pinfunction "RX_6") (pintype "bidirectional"))
    )
    (net (code "137") (name "unconnected-(CH-XO-Pad14)") (class "Default")
      (node (ref "CH") (pin "14") (pinfunction "XO_14") (pintype "bidirectional"))
    )
    (net (code "138") (name "unconnected-(CH-~{ACT}-Pad24)") (class "Default")
      (node (ref "CH") (pin "24") (pinfunction "~{ACT}_24") (pintype "bidirectional"))
    )
    (net (code "139") (name "unconnected-(CH-~{RST}-Pad26)") (class "Default")
      (node (ref "CH") (pin "26") (pinfunction "~{RST}_26") (pintype "bidirectional"))
    )
    (net (code "140") (name "unconnected-(CPLD-IO30-Pad30)") (class "Default")
      (node (ref "CPLD") (pin "30") (pinfunction "IO30_30") (pintype "bidirectional"))
    )
    (net (code "141") (name "unconnected-(CPLD-IO32-Pad32)") (class "Default")
      (node (ref "CPLD") (pin "32") (pinfunction "IO32_32") (pintype "bidirectional"))
    )
    (net (code "142") (name "unconnected-(CPLD-IO41-Pad41)") (class "Default")
      (node (ref "CPLD") (pin "41") (pinfunction "IO41_41") (pintype "bidirectional"))
    )
    (net (code "143") (name "unconnected-(CPLD-IO42-Pad42)") (class "Default")
      (node (ref "CPLD") (pin "42") (pinfunction "IO42_42") (pintype "bidirectional"))
    )
    (net (code "144") (name "unconnected-(CPLD-IO43-Pad43)") (class "Default")
      (node (ref "CPLD") (pin "43") (pinfunction "IO43_43") (pintype "bidirectional"))
    )
    (net (code "145") (name "unconnected-(CPLD-IO46-Pad46)") (class "Default")
      (node (ref "CPLD") (pin "46") (pinfunction "IO46_46") (pintype "bidirectional"))
    )
    (net (code "146") (name "unconnected-(CPLD-IO49-Pad49)") (class "Default")
      (node (ref "CPLD") (pin "49") (pinfunction "IO49_49") (pintype "bidirectional"))
    )
    (net (code "147") (name "unconnected-(CPLD-IO52-Pad52)") (class "Default")
      (node (ref "CPLD") (pin "52") (pinfunction "IO52_52") (pintype "bidirectional"))
    )
    (net (code "148") (name "unconnected-(CPLD-IO59-Pad59)") (class "Default")
      (node (ref "CPLD") (pin "59") (pinfunction "IO59_59") (pintype "bidirectional"))
    )
    (net (code "149") (name "unconnected-(CPLD-IO61-Pad61)") (class "Default")
      (node (ref "CPLD") (pin "61") (pinfunction "IO61_61") (pintype "bidirectional"))
    )
    (net (code "150") (name "unconnected-(CPLD-IO67-Pad67)") (class "Default")
      (node (ref "CPLD") (pin "67") (pinfunction "IO67_67") (pintype "bidirectional"))
    )
    (net (code "151") (name "unconnected-(CPLD-IO70-Pad70)") (class "Default")
      (node (ref "CPLD") (pin "70") (pinfunction "IO70_70") (pintype "bidirectional"))
    )
    (net (code "152") (name "unconnected-(CPLD-IO72-Pad72)") (class "Default")
      (node (ref "CPLD") (pin "72") (pinfunction "IO72_72") (pintype "bidirectional"))
    )
    (net (code "153") (name "unconnected-(FT2232H-ACBUS4-Pad30)") (class "Default")
      (node (ref "FT2232H") (pin "30") (pinfunction "ACBUS4_30") (pintype "bidirectional"))
    )
    (net (code "154") (name "unconnected-(FT2232H-ACBUS5-Pad32)") (class "Default")
      (node (ref "FT2232H") (pin "32") (pinfunction "ACBUS5_32") (pintype "bidirectional"))
    )
    (net (code "155") (name "unconnected-(FT2232H-ACBUS6-Pad33)") (class "Default")
      (node (ref "FT2232H") (pin "33") (pinfunction "ACBUS6_33") (pintype "bidirectional"))
    )
    (net (code "156") (name "unconnected-(FT2232H-ACBUS7-Pad34)") (class "Default")
      (node (ref "FT2232H") (pin "34") (pinfunction "ACBUS7_34") (pintype "bidirectional"))
    )
    (net (code "157") (name "unconnected-(FT2232H-BCBUS4-Pad55)") (class "Default")
      (node (ref "FT2232H") (pin "55") (pinfunction "BCBUS4_55") (pintype "bidirectional"))
    )
    (net (code "158") (name "unconnected-(FT2232H-BCBUS5-Pad57)") (class "Default")
      (node (ref "FT2232H") (pin "57") (pinfunction "BCBUS5_57") (pintype "bidirectional"))
    )
    (net (code "159") (name "unconnected-(FT2232H-BCBUS6-Pad58)") (class "Default")
      (node (ref "FT2232H") (pin "58") (pinfunction "BCBUS6_58") (pintype "bidirectional"))
    )
    (net (code "160") (name "unconnected-(FT2232H-BCBUS7-Pad59)") (class "Default")
      (node (ref "FT2232H") (pin "59") (pinfunction "BCBUS7_59") (pintype "bidirectional"))
    )
    (net (code "161") (name "unconnected-(FT2232H-OSCO-Pad3)") (class "Default")
      (node (ref "FT2232H") (pin "3") (pinfunction "OSCO_3") (pintype "bidirectional"))
    )
    (net (code "162") (name "unconnected-(FT2232H-PWREN#-Pad60)") (class "Default")
      (node (ref "FT2232H") (pin "60") (pinfunction "PWREN#_60") (pintype "bidirectional"))
    )
    (net (code "163") (name "unconnected-(FT2232H-SUSPEND#-Pad36)") (class "Default")
      (node (ref "FT2232H") (pin "36") (pinfunction "SUSPEND#_36") (pintype "bidirectional"))
    )
    (net (code "164") (name "unconnected-(PIOAH-S-Pad33)") (class "Default")
      (node (ref "PIO") (pin "33") (pinfunction "S_33") (pintype "passive"))
    )
    (net (code "165") (name "unconnected-(PIOAI-S-Pad32)") (class "Default")
      (node (ref "PIO") (pin "32") (pinfunction "S_32") (pintype "passive"))
    )
    (net (code "166") (name "unconnected-(PIOAL-S-Pad11)") (class "Default")
      (node (ref "PIO") (pin "11") (pinfunction "S_11") (pintype "passive"))
    )
    (net (code "167") (name "unconnected-(PIOAM-S-Pad45)") (class "Default")
      (node (ref "PIO") (pin "45") (pinfunction "S_45") (pintype "passive"))
    )
    (net (code "168") (name "unconnected-(PIOAN-S-Pad12)") (class "Default")
      (node (ref "PIO") (pin "12") (pinfunction "S_12") (pintype "passive"))
    )
    (net (code "169") (name "unconnected-(PIOAO-S-Pad46)") (class "Default")
      (node (ref "PIO") (pin "46") (pinfunction "S_46") (pintype "passive"))
    )
    (net (code "170") (name "unconnected-(PIOAP-S-Pad13)") (class "Default")
      (node (ref "PIO") (pin "13") (pinfunction "S_13") (pintype "passive"))
    )
    (net (code "171") (name "unconnected-(PIOAQ-S-Pad47)") (class "Default")
      (node (ref "PIO") (pin "47") (pinfunction "S_47") (pintype "passive"))
    )
    (net (code "172") (name "unconnected-(PIOAX-S-Pad10)") (class "Default")
      (node (ref "PIO") (pin "10") (pinfunction "S_10") (pintype "passive"))
    )
    (net (code "173") (name "unconnected-(PIOAY-S-Pad44)") (class "Default")
      (node (ref "PIO") (pin "44") (pinfunction "S_44") (pintype "passive"))
    )
    (net (code "174") (name "unconnected-(PIOBJ-S-Pad66)") (class "Default")
      (node (ref "PIO") (pin "66") (pinfunction "S_66") (pintype "passive"))
    )
    (net (code "175") (name "unconnected-(PIOBL-S-Pad67)") (class "Default")
      (node (ref "PIO") (pin "67") (pinfunction "S_67") (pintype "passive"))
    )
    (net (code "176") (name "unconnected-(PIOC-S-Pad65)") (class "Default")
      (node (ref "PIO") (pin "65") (pinfunction "S_65") (pintype "passive"))
    )
    (net (code "177") (name "unconnected-(PIOE-S-Pad31)") (class "Default")
      (node (ref "PIO") (pin "31") (pinfunction "S_31") (pintype "passive"))
    )
    (net (code "178") (name "unconnected-(PIOZ-S-Pad63)") (class "Default")
      (node (ref "PIO") (pin "63") (pinfunction "S_63") (pintype "passive"))
    )
    (net (code "179") (name "unconnected-(X1-Pad4)") (class "Default")
      (node (ref "X1") (pin "4") (pinfunction "4_4") (pintype "input"))
    )
  )
)
